# Main_board_V6_0.net
KiCad netlist of a schematic drawn in EAGLE
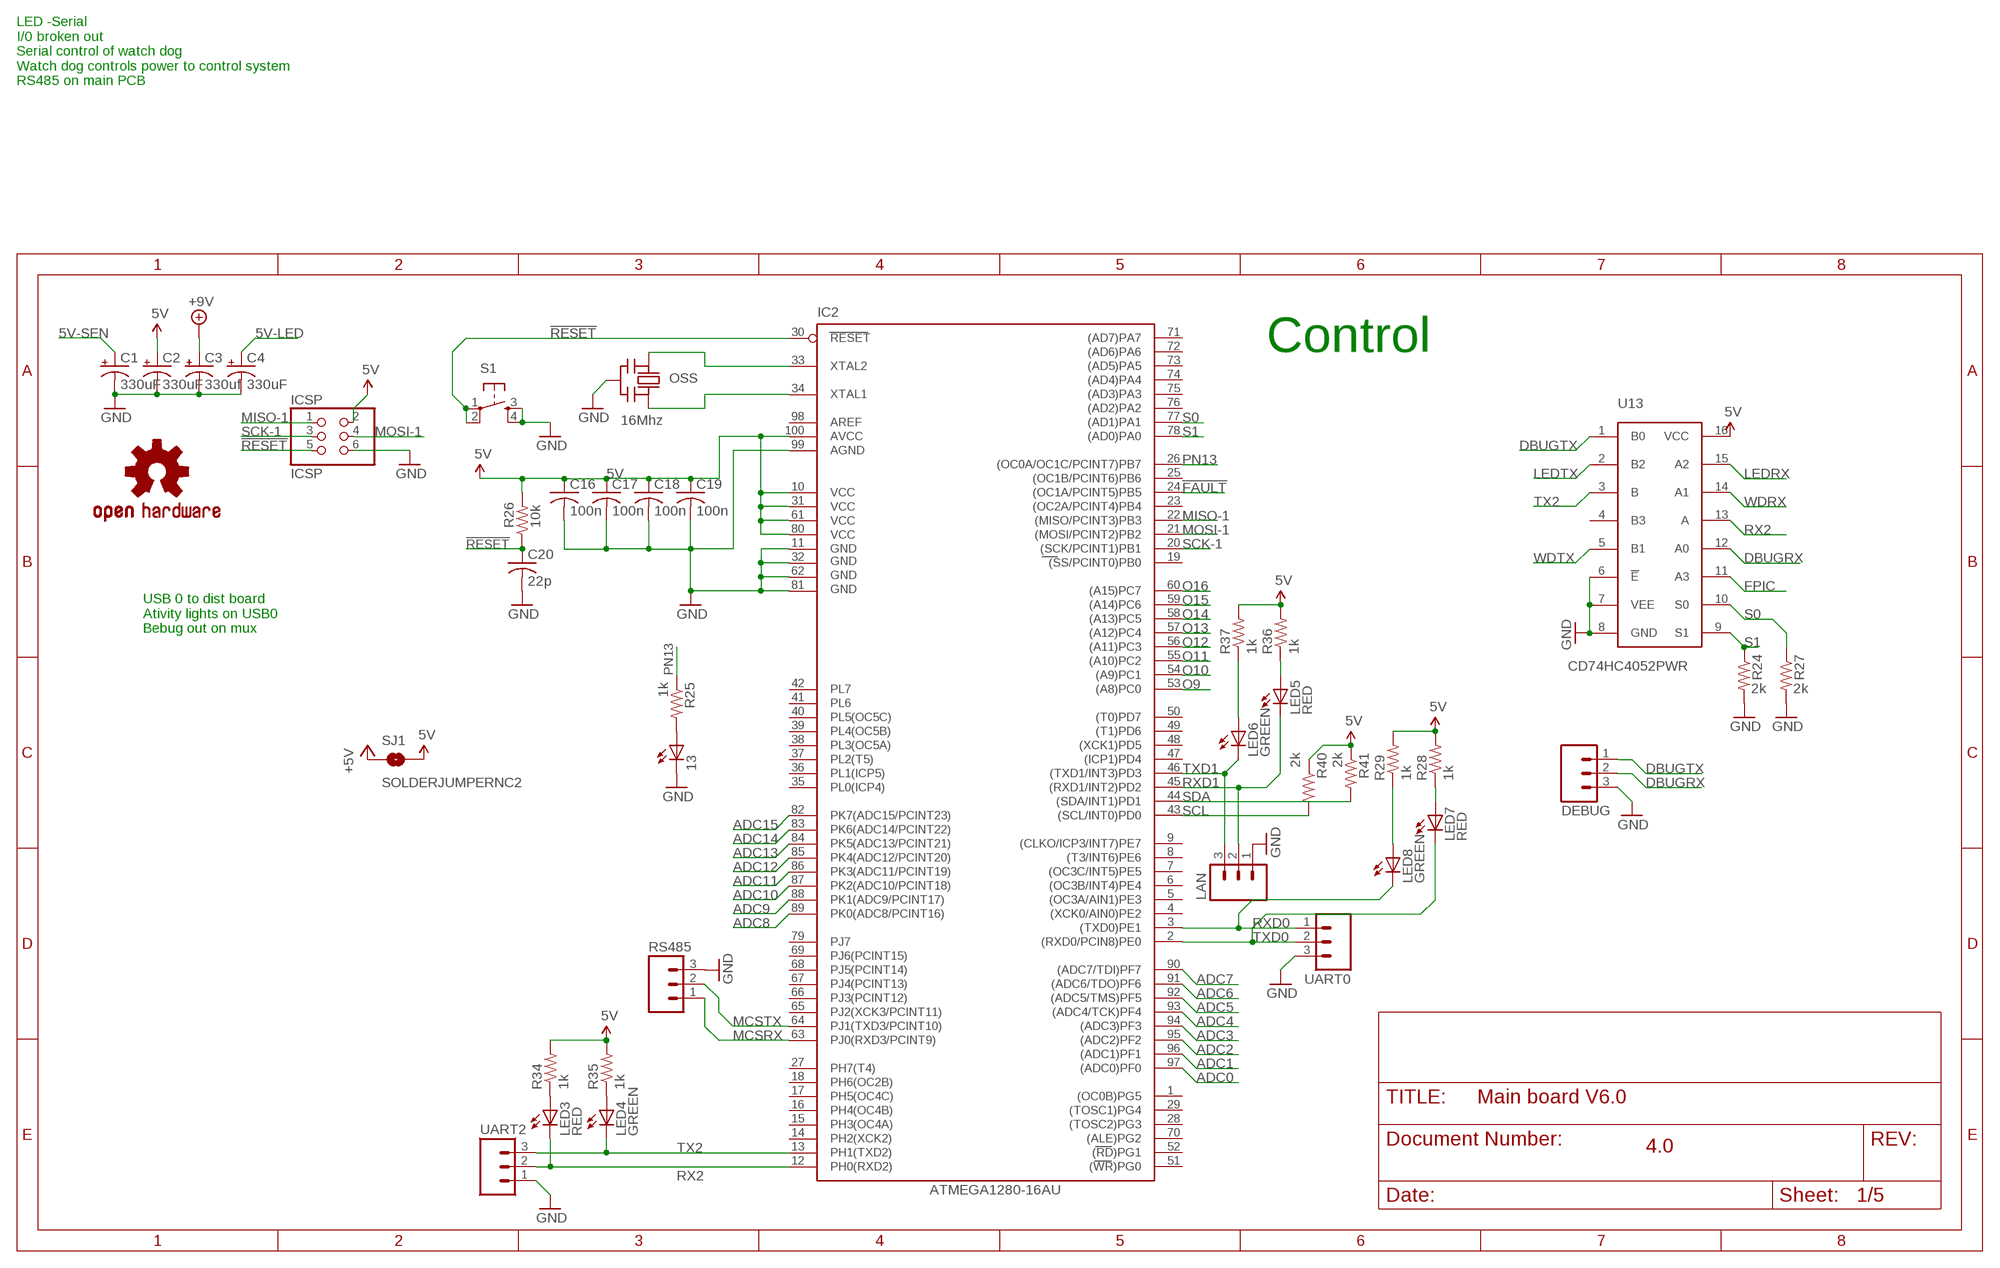
[diagram p0: schematic, sheet 1]
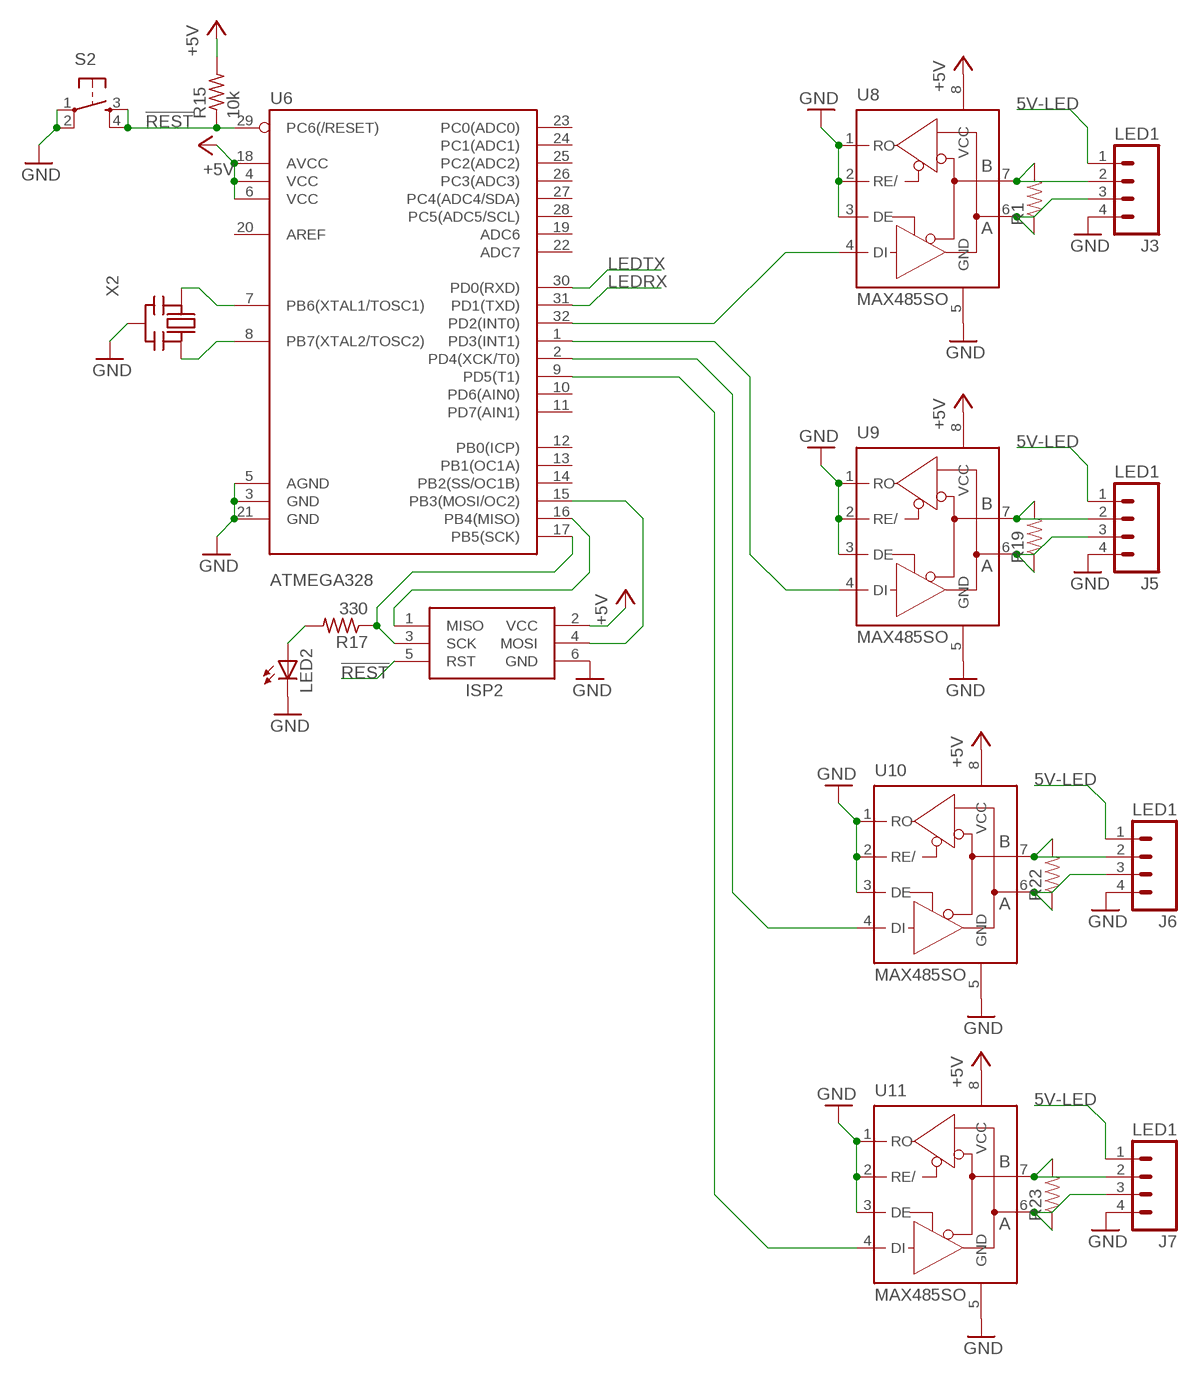
[diagram p1: schematic, sheet 2]
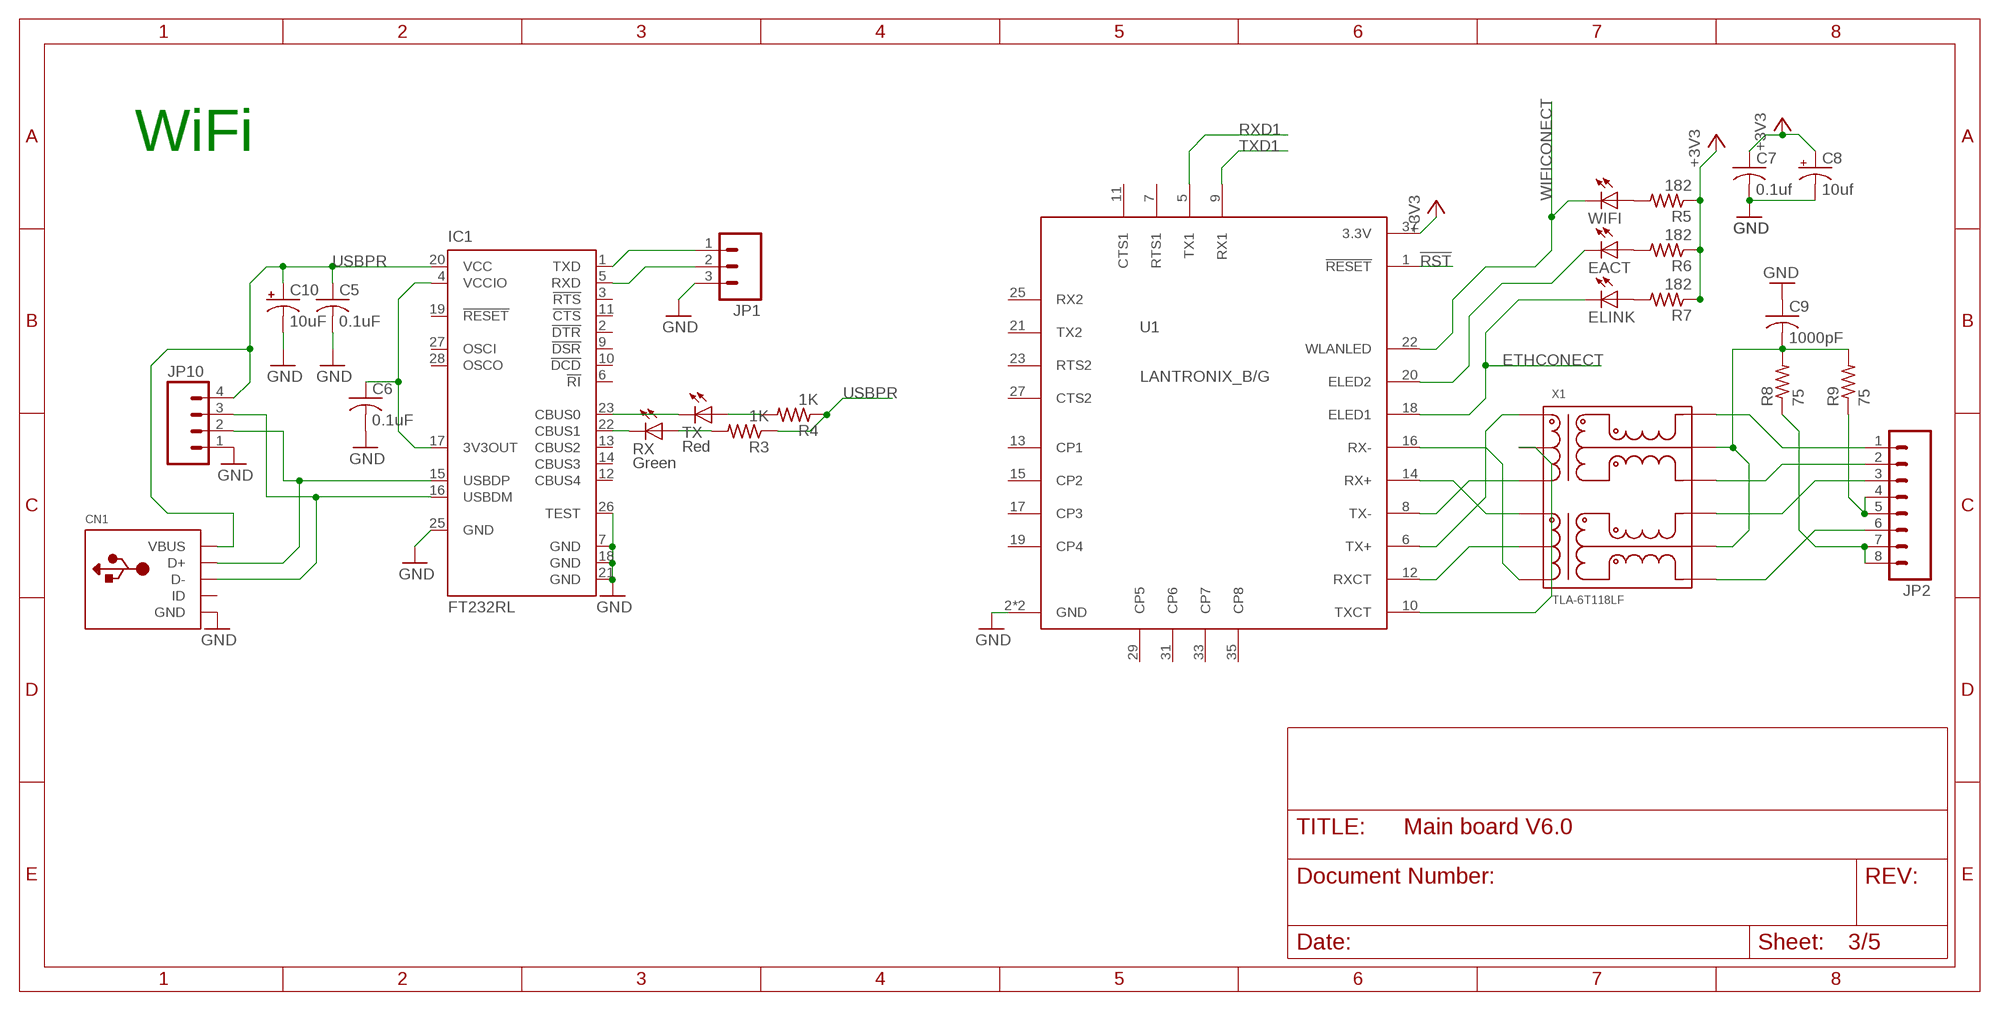
[diagram p2: schematic, sheet 3]
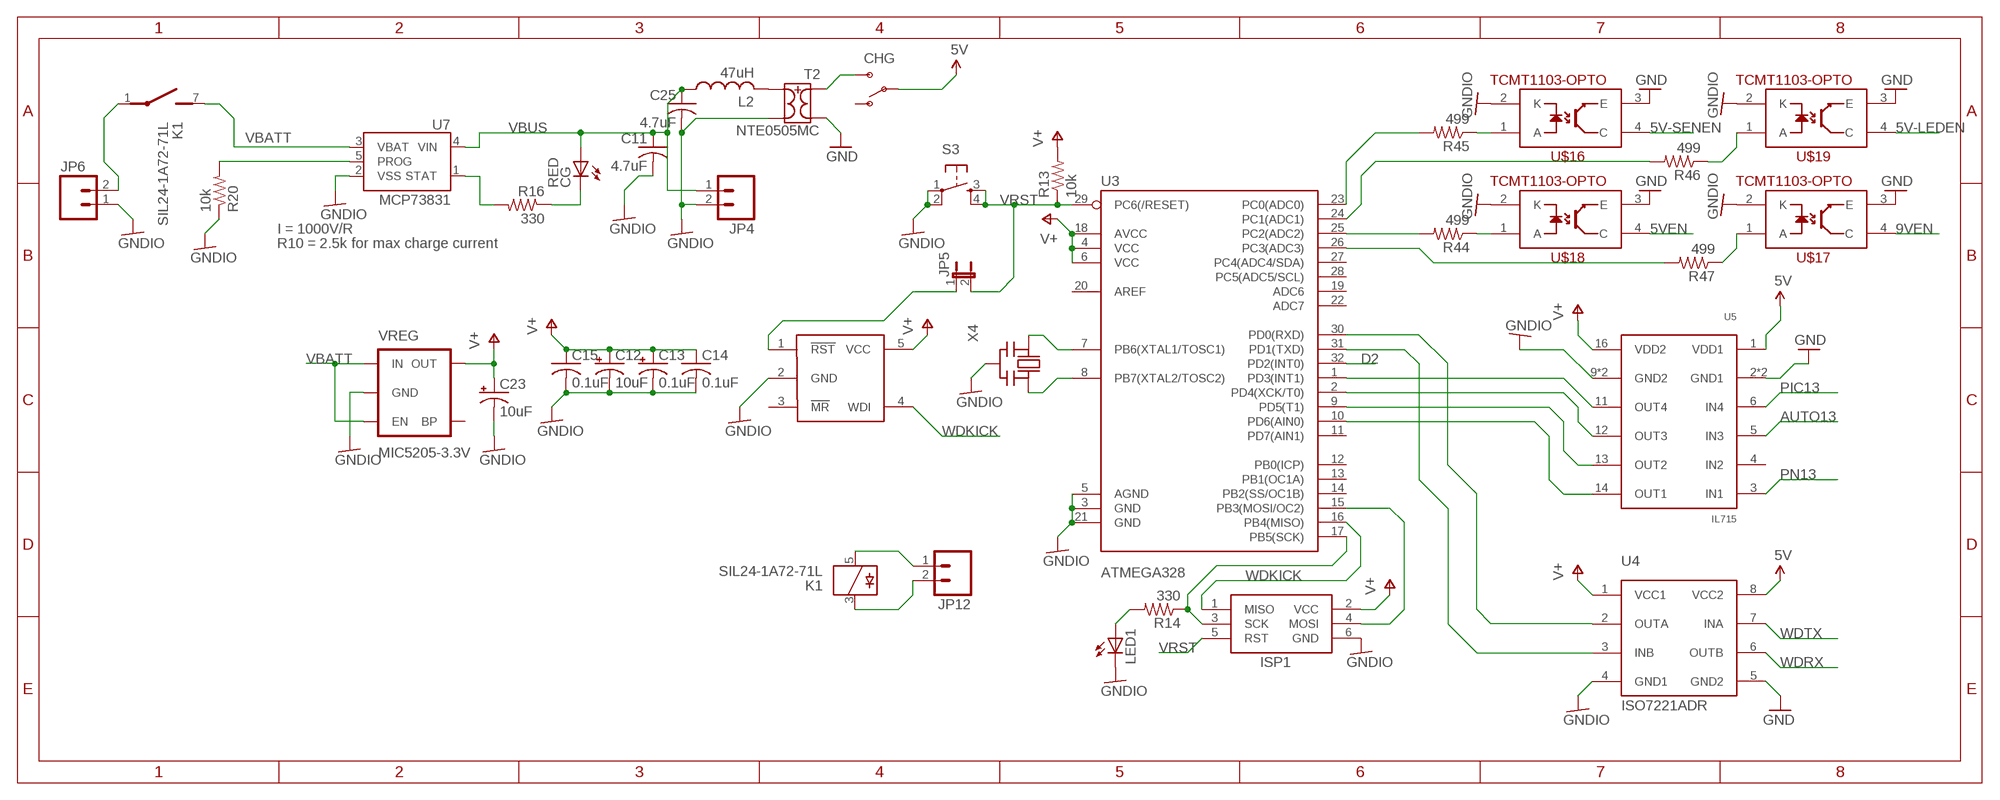
[diagram p3: schematic, sheet 4]
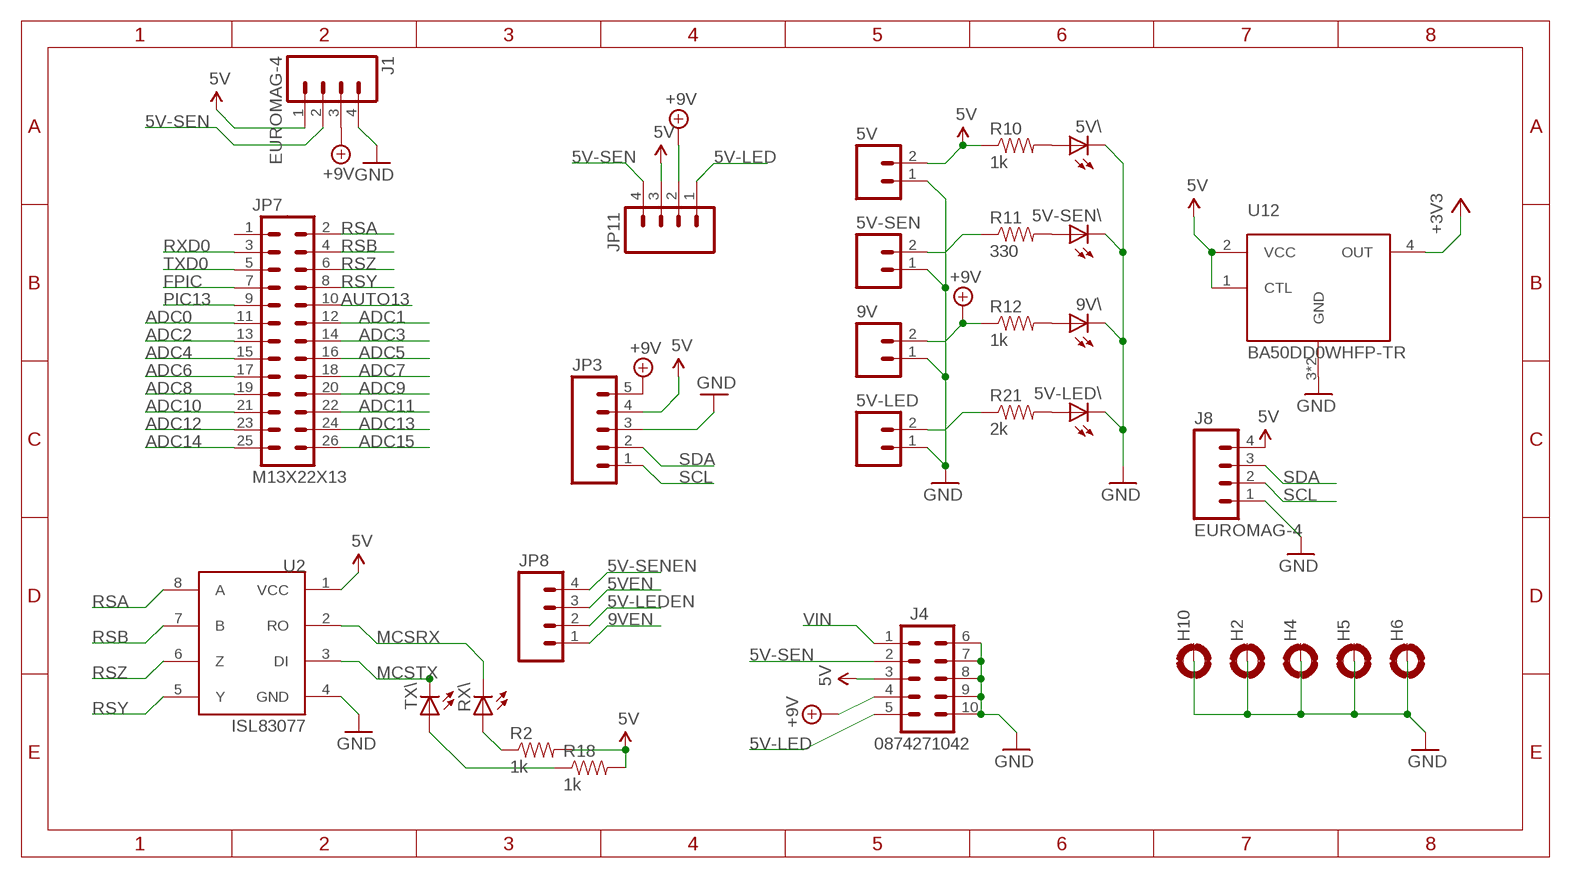
[diagram p4: schematic, sheet 5]

(export (version "E")
  (design (tool "Eeschema 10.0.6"))
  (components
    (comp (ref "5V")
      (value "EUROMAG-290DEG")
      (footprint "eagle-import:M2")
      (libsource (lib "eagle-import") (part "EUROMAG-290DEG"))
    )
    (comp (ref "5V-LED")
      (value "EUROMAG-290DEG")
      (footprint "eagle-import:M2")
      (libsource (lib "eagle-import") (part "EUROMAG-290DEG"))
    )
    (comp (ref "5V-LED\\")
      (value "LEDCHIP-LED0805")
      (footprint "eagle-import:CHIP-LED0805")
      (libsource (lib "eagle-import") (part "LEDCHIP-LED0805"))
    )
    (comp (ref "5V-SEN")
      (value "EUROMAG-290DEG")
      (footprint "eagle-import:M2")
      (libsource (lib "eagle-import") (part "EUROMAG-290DEG"))
    )
    (comp (ref "5V-SEN\\")
      (value "LEDCHIP-LED0805")
      (footprint "eagle-import:CHIP-LED0805")
      (libsource (lib "eagle-import") (part "LEDCHIP-LED0805"))
    )
    (comp (ref "5V\\")
      (value "LEDCHIP-LED0805")
      (footprint "eagle-import:CHIP-LED0805")
      (libsource (lib "eagle-import") (part "LEDCHIP-LED0805"))
    )
    (comp (ref "9V")
      (value "EUROMAG-290DEG")
      (footprint "eagle-import:M2")
      (libsource (lib "eagle-import") (part "EUROMAG-290DEG"))
    )
    (comp (ref "9V\\")
      (value "LEDCHIP-LED0805")
      (footprint "eagle-import:CHIP-LED0805")
      (libsource (lib "eagle-import") (part "LEDCHIP-LED0805"))
    )
    (comp (ref "H2")
      (value "MOUNT-PAD-ROUND2.8")
      (footprint "eagle-import:2,8-PAD")
      (libsource (lib "eagle-import") (part "MOUNT-PAD-ROUND2.8"))
    )
    (comp (ref "H4")
      (value "MOUNT-PAD-ROUND2.8")
      (footprint "eagle-import:2,8-PAD")
      (libsource (lib "eagle-import") (part "MOUNT-PAD-ROUND2.8"))
    )
    (comp (ref "H5")
      (value "MOUNT-PAD-ROUND2.8")
      (footprint "eagle-import:2,8-PAD")
      (libsource (lib "eagle-import") (part "MOUNT-PAD-ROUND2.8"))
    )
    (comp (ref "H6")
      (value "MOUNT-PAD-ROUND2.8")
      (footprint "eagle-import:2,8-PAD")
      (libsource (lib "eagle-import") (part "MOUNT-PAD-ROUND2.8"))
    )
    (comp (ref "H10")
      (value "MOUNT-PAD-ROUND2.8")
      (footprint "eagle-import:2,8-PAD")
      (libsource (lib "eagle-import") (part "MOUNT-PAD-ROUND2.8"))
    )
    (comp (ref "J1")
      (value "EUROMAG-4")
      (footprint "eagle-import:M4")
      (libsource (lib "eagle-import") (part "EUROMAG-4"))
    )
    (comp (ref "J4")
      (value "0874271042")
      (footprint "eagle-import:0874271042")
      (libsource (lib "eagle-import") (part "0874271042"))
    )
    (comp (ref "J8")
      (value "EUROMAG-4")
      (footprint "eagle-import:M4")
      (libsource (lib "eagle-import") (part "EUROMAG-4"))
    )
    (comp (ref "JP3")
      (value "M05LOCK_LONGPADS")
      (footprint "eagle-import:1X05_LOCK_LONGPADS")
      (libsource (lib "eagle-import") (part "M05LOCK_LONGPADS"))
    )
    (comp (ref "JP7")
      (value "M13X22X13")
      (footprint "eagle-import:2X13")
      (libsource (lib "eagle-import") (part "M13X22X13"))
    )
    (comp (ref "JP8")
      (value "M04LOCK")
      (footprint "eagle-import:1X04_LOCK")
      (libsource (lib "eagle-import") (part "SparkFun-Connectors_M04LOCK"))
    )
    (comp (ref "JP11")
      (value "M04POLAR")
      (footprint "eagle-import:MOLEX-1X4")
      (libsource (lib "eagle-import") (part "M04POLAR"))
    )
    (comp (ref "R2")
      (value "1k")
      (footprint "eagle-import:0805")
      (libsource (lib "eagle-import") (part "SparkFun-Passives_RESISTOR0805-RES"))
    )
    (comp (ref "R10")
      (value "1k")
      (footprint "eagle-import:0805")
      (libsource (lib "eagle-import") (part "RESISTOR0805-RES"))
    )
    (comp (ref "R11")
      (value "330")
      (footprint "eagle-import:0805")
      (libsource (lib "eagle-import") (part "RESISTOR0805-RES"))
    )
    (comp (ref "R12")
      (value "1k")
      (footprint "eagle-import:0805")
      (libsource (lib "eagle-import") (part "RESISTOR0805-RES"))
    )
    (comp (ref "R18")
      (value "1k")
      (footprint "eagle-import:0805")
      (libsource (lib "eagle-import") (part "SparkFun-Passives_RESISTOR0805-RES"))
    )
    (comp (ref "R21")
      (value "2k")
      (footprint "eagle-import:0805")
      (libsource (lib "eagle-import") (part "RESISTOR0805-RES"))
    )
    (comp (ref "RX\\")
      (value "LEDCHIP-LED0805")
      (footprint "eagle-import:CHIP-LED0805")
      (libsource (lib "eagle-import") (part "LEDCHIP-LED0805"))
    )
    (comp (ref "TX\\")
      (value "LEDCHIP-LED0805")
      (footprint "eagle-import:CHIP-LED0805")
      (libsource (lib "eagle-import") (part "LEDCHIP-LED0805"))
    )
    (comp (ref "U2")
      (value "ISL83077")
      (footprint "eagle-import:SO08")
      (libsource (lib "eagle-import") (part "ISL83077"))
    )
    (comp (ref "U12")
      (value "BA50DD0WHFP-TR")
      (footprint "eagle-import:HRP5")
      (libsource (lib "eagle-import") (part "BA50DD0WHFP-TR"))
    )
    (comp (ref "ISP2")
      (value "AVRISP-6")
      (footprint "eagle-import:AVRISP")
      (libsource (lib "eagle-import") (part "AVRISP-6"))
    )
    (comp (ref "J3")
      (value "LED1")
      (footprint "eagle-import:M4")
      (libsource (lib "eagle-import") (part "EUROMAG-4"))
    )
    (comp (ref "J5")
      (value "LED1")
      (footprint "eagle-import:M4")
      (libsource (lib "eagle-import") (part "EUROMAG-4"))
    )
    (comp (ref "J6")
      (value "LED1")
      (footprint "eagle-import:M4")
      (libsource (lib "eagle-import") (part "EUROMAG-4"))
    )
    (comp (ref "J7")
      (value "LED1")
      (footprint "eagle-import:M4")
      (libsource (lib "eagle-import") (part "EUROMAG-4"))
    )
    (comp (ref "LED2")
      (value "LEDCHIPLED_0805")
      (footprint "eagle-import:CHIPLED_0805")
      (libsource (lib "eagle-import") (part "LEDCHIPLED_0805"))
    )
    (comp (ref "R1")
      (value "RESISTOR0805-RES")
      (footprint "eagle-import:0805")
      (libsource (lib "eagle-import") (part "SparkFun-Passives_RESISTOR0805-RES"))
    )
    (comp (ref "R15")
      (value "10k")
      (footprint "eagle-import:R0805")
      (libsource (lib "eagle-import") (part "resistor_R-US_R0805"))
    )
    (comp (ref "R17")
      (value "330")
      (footprint "eagle-import:R0805")
      (libsource (lib "eagle-import") (part "resistor_R-US_R0805"))
    )
    (comp (ref "R19")
      (value "RESISTOR0805-RES")
      (footprint "eagle-import:0805")
      (libsource (lib "eagle-import") (part "SparkFun-Passives_RESISTOR0805-RES"))
    )
    (comp (ref "R22")
      (value "RESISTOR0805-RES")
      (footprint "eagle-import:0805")
      (libsource (lib "eagle-import") (part "SparkFun-Passives_RESISTOR0805-RES"))
    )
    (comp (ref "R23")
      (value "RESISTOR0805-RES")
      (footprint "eagle-import:0805")
      (libsource (lib "eagle-import") (part "SparkFun-Passives_RESISTOR0805-RES"))
    )
    (comp (ref "S2")
      (value "TAC_SWITCHPTH")
      (footprint "eagle-import:TACTILE-PTH")
      (libsource (lib "eagle-import") (part "TAC_SWITCHPTH"))
    )
    (comp (ref "U6")
      (value "ATMEGA328")
      (footprint "eagle-import:TQFP32-08")
      (libsource (lib "eagle-import") (part "ATMEGA168"))
    )
    (comp (ref "U8")
      (value "MAX485SO")
      (footprint "eagle-import:SO08")
      (libsource (lib "eagle-import") (part "MAX485SO"))
    )
    (comp (ref "U9")
      (value "MAX485SO")
      (footprint "eagle-import:SO08")
      (libsource (lib "eagle-import") (part "MAX485SO"))
    )
    (comp (ref "U10")
      (value "MAX485SO")
      (footprint "eagle-import:SO08")
      (libsource (lib "eagle-import") (part "MAX485SO"))
    )
    (comp (ref "U11")
      (value "MAX485SO")
      (footprint "eagle-import:SO08")
      (libsource (lib "eagle-import") (part "MAX485SO"))
    )
    (comp (ref "X2")
      (value "CERMOSCILL-AWCSR")
      (footprint "eagle-import:AWCSR")
      (libsource (lib "eagle-import") (part "CERMOSCILL-AWCSR"))
    )
    (comp (ref "C5")
      (value "0.1uF")
      (footprint "eagle-import:C0805K")
      (libsource (lib "eagle-import") (part "C-USC0805K"))
    )
    (comp (ref "C6")
      (value "0.1uF")
      (footprint "eagle-import:C0805K")
      (libsource (lib "eagle-import") (part "C-USC0805K"))
    )
    (comp (ref "C7")
      (value "0.1uf")
      (footprint "eagle-import:C0805K")
      (libsource (lib "eagle-import") (part "C-USC0805K"))
    )
    (comp (ref "C8")
      (value "10uf")
      (footprint "eagle-import:EIA3528")
      (libsource (lib "eagle-import") (part "CAP_POL3528"))
    )
    (comp (ref "C9")
      (value "1000pF")
      (footprint "eagle-import:C1812")
      (libsource (lib "eagle-import") (part "C-USC1812"))
    )
    (comp (ref "C10")
      (value "10uF")
      (footprint "eagle-import:EIA3528-KIT")
      (libsource (lib "eagle-import") (part "CAP_POL3528-KIT"))
    )
    (comp (ref "CN1")
      (value "USBMINIB")
      (footprint "eagle-import:USB-MINIB")
      (libsource (lib "eagle-import") (part "USBMINIB"))
    )
    (comp (ref "EACT")
      (value "LEDCHIP-LED0805")
      (footprint "eagle-import:CHIP-LED0805")
      (libsource (lib "eagle-import") (part "LEDCHIP-LED0805"))
    )
    (comp (ref "ELINK")
      (value "LEDCHIP-LED0805")
      (footprint "eagle-import:CHIP-LED0805")
      (libsource (lib "eagle-import") (part "LEDCHIP-LED0805"))
    )
    (comp (ref "IC1")
      (value "FT232RL")
      (footprint "eagle-import:SSOP28")
      (libsource (lib "eagle-import") (part "FT232RL"))
    )
    (comp (ref "JP1")
      (value "M03POLAR")
      (footprint "eagle-import:MOLEX-1X3")
      (libsource (lib "eagle-import") (part "M03POLAR"))
    )
    (comp (ref "JP2")
      (value "M08LOCK")
      (footprint "eagle-import:1X08_LOCK")
      (libsource (lib "eagle-import") (part "M08LOCK"))
    )
    (comp (ref "JP10")
      (value "M04POLAR")
      (footprint "eagle-import:MOLEX-1X4")
      (libsource (lib "eagle-import") (part "M04POLAR"))
    )
    (comp (ref "R3")
      (value "1K")
      (footprint "eagle-import:R0805")
      (libsource (lib "eagle-import") (part "R-US_R0805"))
    )
    (comp (ref "R4")
      (value "1K")
      (footprint "eagle-import:R0805")
      (libsource (lib "eagle-import") (part "R-US_R0805"))
    )
    (comp (ref "R5")
      (value "182")
      (footprint "eagle-import:R0805")
      (libsource (lib "eagle-import") (part "R-US_R0805"))
    )
    (comp (ref "R6")
      (value "182")
      (footprint "eagle-import:R0805")
      (libsource (lib "eagle-import") (part "R-US_R0805"))
    )
    (comp (ref "R7")
      (value "182")
      (footprint "eagle-import:R0805")
      (libsource (lib "eagle-import") (part "R-US_R0805"))
    )
    (comp (ref "R8")
      (value "75")
      (footprint "eagle-import:R0805")
      (libsource (lib "eagle-import") (part "R-US_R0805"))
    )
    (comp (ref "R9")
      (value "75")
      (footprint "eagle-import:R0805")
      (libsource (lib "eagle-import") (part "R-US_R0805"))
    )
    (comp (ref "RX")
      (value "Green")
      (footprint "eagle-import:CHIP-LED0805")
      (libsource (lib "eagle-import") (part "LEDCHIP-LED0805"))
    )
    (comp (ref "TX")
      (value "Red")
      (footprint "eagle-import:CHIP-LED0805")
      (libsource (lib "eagle-import") (part "LEDCHIP-LED0805"))
    )
    (comp (ref "U1")
      (value "LANTRONIX_B/G")
      (footprint "eagle-import:LANA_BTH")
      (libsource (lib "eagle-import") (part "LANTRONIX_A/B"))
    )
    (comp (ref "WIFI")
      (value "LEDCHIP-LED0805")
      (footprint "eagle-import:CHIP-LED0805")
      (libsource (lib "eagle-import") (part "LEDCHIP-LED0805"))
    )
    (comp (ref "X1")
      (value "TLA-6T118LF")
      (footprint "eagle-import:SO-16MOD")
      (libsource (lib "eagle-import") (part "TLA-6T118LF"))
    )
    (comp (ref "13")
      (value "LEDCHIP-LED0805")
      (footprint "eagle-import:CHIP-LED0805")
      (libsource (lib "eagle-import") (part "LEDCHIP-LED0805"))
    )
    (comp (ref "C1")
      (value "330uF")
      (footprint "eagle-import:140CLH-0810")
      (libsource (lib "eagle-import") (part "CPOL-US140CLH-0810"))
    )
    (comp (ref "C2")
      (value "330uF")
      (footprint "eagle-import:140CLH-0810")
      (libsource (lib "eagle-import") (part "CPOL-US140CLH-0810"))
    )
    (comp (ref "C3")
      (value "330uf")
      (footprint "eagle-import:140CLH-0810")
      (libsource (lib "eagle-import") (part "CPOL-US140CLH-0810"))
    )
    (comp (ref "C4")
      (value "330uF")
      (footprint "eagle-import:140CLH-0810")
      (libsource (lib "eagle-import") (part "CPOL-US140CLH-0810"))
    )
    (comp (ref "C16")
      (value "100n")
      (footprint "eagle-import:C0805")
      (libsource (lib "eagle-import") (part "C-USC0805"))
    )
    (comp (ref "C17")
      (value "100n")
      (footprint "eagle-import:C0805")
      (libsource (lib "eagle-import") (part "C-USC0805"))
    )
    (comp (ref "C18")
      (value "100n")
      (footprint "eagle-import:C0805")
      (libsource (lib "eagle-import") (part "C-USC0805"))
    )
    (comp (ref "C19")
      (value "100n")
      (footprint "eagle-import:C0805")
      (libsource (lib "eagle-import") (part "C-USC0805"))
    )
    (comp (ref "C20")
      (value "22p")
      (footprint "eagle-import:C0805")
      (libsource (lib "eagle-import") (part "C-USC0805"))
    )
    (comp (ref "DEBUG")
      (value "M03LOCK")
      (footprint "eagle-import:1X03_LOCK")
      (libsource (lib "eagle-import") (part "M03LOCK"))
    )
    (comp (ref "IC2")
      (value "ATMEGA1280-16AU")
      (footprint "eagle-import:TQFP100")
      (libsource (lib "eagle-import") (part "ATMEGAAU1280-16"))
    )
    (comp (ref "ICSP")
      (value "ICSP")
      (footprint "eagle-import:2X03")
      (libsource (lib "eagle-import") (part "PINHD-2X3"))
    )
    (comp (ref "LAN")
      (value "M03LOCK")
      (footprint "eagle-import:1X03_LOCK")
      (libsource (lib "eagle-import") (part "M03LOCK"))
    )
    (comp (ref "LED3")
      (value "RED")
      (footprint "eagle-import:CHIP-LED0805")
      (libsource (lib "eagle-import") (part "LEDCHIP-LED0805"))
    )
    (comp (ref "LED4")
      (value "GREEN")
      (footprint "eagle-import:CHIP-LED0805")
      (libsource (lib "eagle-import") (part "LEDCHIP-LED0805"))
    )
    (comp (ref "LED5")
      (value "RED")
      (footprint "eagle-import:CHIP-LED0805")
      (libsource (lib "eagle-import") (part "LEDCHIP-LED0805"))
    )
    (comp (ref "LED6")
      (value "GREEN")
      (footprint "eagle-import:CHIP-LED0805")
      (libsource (lib "eagle-import") (part "LEDCHIP-LED0805"))
    )
    (comp (ref "LED7")
      (value "RED")
      (footprint "eagle-import:CHIP-LED0805")
      (libsource (lib "eagle-import") (part "LEDCHIP-LED0805"))
    )
    (comp (ref "LED8")
      (value "GREEN")
      (footprint "eagle-import:CHIP-LED0805")
      (libsource (lib "eagle-import") (part "LEDCHIP-LED0805"))
    )
    (comp (ref "OSS")
      (value "16Mhz")
      (footprint "eagle-import:AWCSR")
      (libsource (lib "eagle-import") (part "CERMOSCILL-AWCSR"))
    )
    (comp (ref "R24")
      (value "2k")
      (footprint "eagle-import:R0805")
      (libsource (lib "eagle-import") (part "R-US_R0805"))
    )
    (comp (ref "R25")
      (value "1k")
      (footprint "eagle-import:R0805")
      (libsource (lib "eagle-import") (part "R-US_R0805"))
    )
    (comp (ref "R26")
      (value "10k")
      (footprint "eagle-import:R0805")
      (libsource (lib "eagle-import") (part "R-US_R0805"))
    )
    (comp (ref "R27")
      (value "2k")
      (footprint "eagle-import:R0805")
      (libsource (lib "eagle-import") (part "R-US_R0805"))
    )
    (comp (ref "R28")
      (value "1k")
      (footprint "eagle-import:R0805")
      (libsource (lib "eagle-import") (part "R-US_R0805"))
    )
    (comp (ref "R29")
      (value "1k")
      (footprint "eagle-import:R0805")
      (libsource (lib "eagle-import") (part "R-US_R0805"))
    )
    (comp (ref "R34")
      (value "1k")
      (footprint "eagle-import:R0805")
      (libsource (lib "eagle-import") (part "R-US_R0805"))
    )
    (comp (ref "R35")
      (value "1k")
      (footprint "eagle-import:R0805")
      (libsource (lib "eagle-import") (part "R-US_R0805"))
    )
    (comp (ref "R36")
      (value "1k")
      (footprint "eagle-import:R0805")
      (libsource (lib "eagle-import") (part "R-US_R0805"))
    )
    (comp (ref "R37")
      (value "1k")
      (footprint "eagle-import:R0805")
      (libsource (lib "eagle-import") (part "R-US_R0805"))
    )
    (comp (ref "R40")
      (value "2k")
      (footprint "eagle-import:R0805")
      (libsource (lib "eagle-import") (part "R-US_R0805"))
    )
    (comp (ref "R41")
      (value "2k")
      (footprint "eagle-import:R0805")
      (libsource (lib "eagle-import") (part "R-US_R0805"))
    )
    (comp (ref "RS485")
      (value "M03LOCK")
      (footprint "eagle-import:1X03_LOCK")
      (libsource (lib "eagle-import") (part "M03LOCK"))
    )
    (comp (ref "S1")
      (value "TAC_SWITCHSMD")
      (footprint "eagle-import:TACTILE_SWITCH_SMD")
      (libsource (lib "eagle-import") (part "TAC_SWITCHSMD"))
    )
    (comp (ref "SJ1")
      (value "SOLDERJUMPERNC2")
      (footprint "eagle-import:SJ_2S-NOTRACE")
      (libsource (lib "eagle-import") (part "SOLDERJUMPERNC2"))
    )
    (comp (ref "U$3")
      (value "OSHW-LOGOL")
      (footprint "eagle-import:OSHW-LOGO-L")
      (libsource (lib "eagle-import") (part "OSHW-LOGOL"))
    )
    (comp (ref "U13")
      (value "CD74HC4052PWR")
      (footprint "eagle-import:TSSOP-16")
      (libsource (lib "eagle-import") (part "CD74HC4052PWR"))
    )
    (comp (ref "UART0")
      (value "M03LOCK")
      (footprint "eagle-import:1X03_LOCK")
      (libsource (lib "eagle-import") (part "M03LOCK"))
    )
    (comp (ref "UART2")
      (value "M03POLAR")
      (footprint "eagle-import:MOLEX-1X3")
      (libsource (lib "eagle-import") (part "M03POLAR"))
    )
    (comp (ref "C11")
      (value "4.7uF")
      (footprint "eagle-import:C0603")
      (libsource (lib "eagle-import") (part "resistor_C-USC0603"))
    )
    (comp (ref "C12")
      (value "10uF")
      (footprint "eagle-import:CT3528")
      (libsource (lib "eagle-import") (part "CPOL-USCT3528"))
    )
    (comp (ref "C13")
      (value "0.1uF")
      (footprint "eagle-import:CT3528")
      (libsource (lib "eagle-import") (part "CPOL-USCT3528"))
    )
    (comp (ref "C14")
      (value "0.1uF")
      (footprint "eagle-import:C0805")
      (libsource (lib "eagle-import") (part "C-USC0805"))
    )
    (comp (ref "C15")
      (value "0.1uF")
      (footprint "eagle-import:C0805")
      (libsource (lib "eagle-import") (part "C-USC0805"))
    )
    (comp (ref "C23")
      (value "10uF")
      (footprint "eagle-import:CT3528")
      (libsource (lib "eagle-import") (part "CPOL-USCT3528"))
    )
    (comp (ref "C25")
      (value "4.7uF")
      (footprint "eagle-import:C0603")
      (libsource (lib "eagle-import") (part "resistor_C-USC0603"))
    )
    (comp (ref "CG")
      (value "RED")
      (footprint "eagle-import:SML0805")
      (libsource (lib "eagle-import") (part "LEDSML0805"))
    )
    (comp (ref "CHG")
      (value "SWITCH-SPSTPTH")
      (footprint "eagle-import:SWITCH-SPDT")
      (libsource (lib "eagle-import") (part "SWITCH-SPSTPTH"))
    )
    (comp (ref "ISP1")
      (value "AVRISP-6")
      (footprint "eagle-import:AVRISP")
      (libsource (lib "eagle-import") (part "AVRISP-6"))
    )
    (comp (ref "JP4")
      (value "M021X02_NO_SILK")
      (footprint "eagle-import:1X02_NO_SILK")
      (libsource (lib "eagle-import") (part "M021X02_NO_SILK"))
    )
    (comp (ref "JP5")
      (value "JUMPER-2PTH_LOCK")
      (footprint "eagle-import:1X02_LOCK")
      (libsource (lib "eagle-import") (part "JUMPER-2PTH_LOCK"))
    )
    (comp (ref "JP6")
      (value "M02-JST-2MM-SMT")
      (footprint "eagle-import:JST-2-SMD")
      (libsource (lib "eagle-import") (part "M02-JST-2MM-SMT"))
    )
    (comp (ref "JP12")
      (value "M02POLAR_LOCK")
      (footprint "eagle-import:MOLEX-1X2_LOCK")
      (libsource (lib "eagle-import") (part "M02POLAR_LOCK"))
    )
    (comp (ref "K1")
      (value "SIL24-1A72-71L")
      (footprint "eagle-import:REED")
      (libsource (lib "eagle-import") (part "35701331"))
    )
    (comp (ref "L2")
      (value "47uH")
      (footprint "eagle-import:L2012C")
      (libsource (lib "eagle-import") (part "L-USL2012C"))
    )
    (comp (ref "LED1")
      (value "LEDCHIPLED_0805")
      (footprint "eagle-import:CHIPLED_0805")
      (libsource (lib "eagle-import") (part "LEDCHIPLED_0805"))
    )
    (comp (ref "R13")
      (value "10k")
      (footprint "eagle-import:R0805")
      (libsource (lib "eagle-import") (part "resistor_R-US_R0805"))
    )
    (comp (ref "R14")
      (value "330")
      (footprint "eagle-import:R0805")
      (libsource (lib "eagle-import") (part "resistor_R-US_R0805"))
    )
    (comp (ref "R16")
      (value "330")
      (footprint "eagle-import:R0805")
      (libsource (lib "eagle-import") (part "resistor_R-US_R0805"))
    )
    (comp (ref "R20")
      (value "10k")
      (footprint "eagle-import:R0805")
      (libsource (lib "eagle-import") (part "resistor_R-US_R0805"))
    )
    (comp (ref "R44")
      (value "499")
      (footprint "eagle-import:R0805")
      (libsource (lib "eagle-import") (part "resistor_R-US_R0805"))
    )
    (comp (ref "R45")
      (value "499")
      (footprint "eagle-import:R0805")
      (libsource (lib "eagle-import") (part "resistor_R-US_R0805"))
    )
    (comp (ref "R46")
      (value "499")
      (footprint "eagle-import:R0805")
      (libsource (lib "eagle-import") (part "resistor_R-US_R0805"))
    )
    (comp (ref "R47")
      (value "499")
      (footprint "eagle-import:R0805")
      (libsource (lib "eagle-import") (part "resistor_R-US_R0805"))
    )
    (comp (ref "S3")
      (value "TAC_SWITCHPTH")
      (footprint "eagle-import:TACTILE-PTH")
      (libsource (lib "eagle-import") (part "TAC_SWITCHPTH"))
    )
    (comp (ref "T2")
      (value "NTE0505MC")
      (footprint "eagle-import:SO-8FT")
      (libsource (lib "eagle-import") (part "NTE0505MC"))
    )
    (comp (ref "U$16")
      (value "TCMT1103-OPTO")
      (footprint "eagle-import:SSOP-4")
      (libsource (lib "eagle-import") (part "TCMT1103-OPTO"))
    )
    (comp (ref "U$17")
      (value "TCMT1103-OPTO")
      (footprint "eagle-import:SSOP-4")
      (libsource (lib "eagle-import") (part "TCMT1103-OPTO"))
    )
    (comp (ref "U$18")
      (value "TCMT1103-OPTO")
      (footprint "eagle-import:SSOP-4")
      (libsource (lib "eagle-import") (part "TCMT1103-OPTO"))
    )
    (comp (ref "U$19")
      (value "TCMT1103-OPTO")
      (footprint "eagle-import:SSOP-4")
      (libsource (lib "eagle-import") (part "TCMT1103-OPTO"))
    )
    (comp (ref "U3")
      (value "ATMEGA328")
      (footprint "eagle-import:TQFP32-08")
      (libsource (lib "eagle-import") (part "ATMEGA168"))
    )
    (comp (ref "U4")
      (value "ISO7221ADR")
      (footprint "eagle-import:SOIC-8")
      (libsource (lib "eagle-import") (part "ISO7221ADR"))
    )
    (comp (ref "U5")
      (value "IL715")
      (footprint "eagle-import:S016")
      (libsource (lib "eagle-import") (part "IL715"))
    )
    (comp (ref "U7")
      (value "MCP73831")
      (footprint "eagle-import:SOT23-5")
      (libsource (lib "eagle-import") (part "MCP73831"))
    )
    (comp (ref "U20")
      (value "MAX823")
      (footprint "eagle-import:SOT23-5L")
      (libsource (lib "eagle-import") (part "MAX823"))
    )
    (comp (ref "VREG")
      (value "MIC5205-3.3V")
      (footprint "eagle-import:SOT23-5")
      (libsource (lib "eagle-import") (part "V_REG_LDOSMD"))
    )
    (comp (ref "X4")
      (value "CERMOSCILL-CSTCRG")
      (footprint "eagle-import:CSTCR-G")
      (libsource (lib "eagle-import") (part "CERMOSCILL-CSTCRG"))
    )
  )
  (nets
    (net (code "1") (name "+3V3") (class "Default")
      (node (ref "C7") (pin "1") (pinfunction "1_1") (pintype "passive"))
      (node (ref "C8") (pin "A") (pinfunction "+_A") (pintype "passive"))
      (node (ref "R5") (pin "1") (pinfunction "1_1") (pintype "passive"))
      (node (ref "R6") (pin "1") (pinfunction "1_1") (pintype "passive"))
      (node (ref "R7") (pin "1") (pinfunction "1_1") (pintype "passive"))
      (node (ref "U1") (pin "37") (pinfunction "3.3V_37") (pintype "bidirectional"))
      (node (ref "U12") (pin "4") (pinfunction "OUT_4") (pintype "bidirectional"))
    )
    (net (code "2") (name "+5V") (class "Default")
      (node (ref "ISP2") (pin "2") (pinfunction "VCC_2") (pintype "power_in"))
      (node (ref "R15") (pin "2") (pinfunction "2_2") (pintype "passive"))
      (node (ref "SJ1") (pin "1") (pinfunction "1_1") (pintype "passive"))
      (node (ref "U10") (pin "8") (pinfunction "VCC_8") (pintype "bidirectional"))
      (node (ref "U11") (pin "8") (pinfunction "VCC_8") (pintype "bidirectional"))
      (node (ref "U6") (pin "18") (pinfunction "AVCC_18") (pintype "bidirectional"))
      (node (ref "U6") (pin "4") (pinfunction "VCC_4") (pintype "bidirectional"))
      (node (ref "U6") (pin "6") (pinfunction "VCC_6") (pintype "bidirectional"))
      (node (ref "U8") (pin "8") (pinfunction "VCC_8") (pintype "bidirectional"))
      (node (ref "U9") (pin "8") (pinfunction "VCC_8") (pintype "bidirectional"))
    )
    (net (code "3") (name "+9V") (class "Default")
      (node (ref "9V") (pin "2") (pinfunction "2_2") (pintype "passive"))
      (node (ref "C3") (pin "+") (pinfunction "+_+") (pintype "passive"))
      (node (ref "J1") (pin "3") (pinfunction "3_3") (pintype "passive"))
      (node (ref "J4") (pin "4") (pinfunction "4_4") (pintype "passive"))
      (node (ref "JP11") (pin "2") (pinfunction "2_2") (pintype "passive"))
      (node (ref "JP3") (pin "5") (pinfunction "5_5") (pintype "passive"))
      (node (ref "R12") (pin "1") (pinfunction "1_1") (pintype "passive"))
    )
    (net (code "4") (name "5V") (class "Default")
      (node (ref "5V") (pin "2") (pinfunction "2_2") (pintype "passive"))
      (node (ref "C16") (pin "1") (pinfunction "1_1") (pintype "passive"))
      (node (ref "C17") (pin "1") (pinfunction "1_1") (pintype "passive"))
      (node (ref "C18") (pin "1") (pinfunction "1_1") (pintype "passive"))
      (node (ref "C19") (pin "1") (pinfunction "1_1") (pintype "passive"))
      (node (ref "C2") (pin "+") (pinfunction "+_+") (pintype "passive"))
      (node (ref "CHG") (pin "2") (pinfunction "P_2") (pintype "passive"))
      (node (ref "IC2") (pin "10") (pinfunction "VCC_10") (pintype "power_in"))
      (node (ref "IC2") (pin "100") (pinfunction "AVCC_100") (pintype "power_in"))
      (node (ref "IC2") (pin "31") (pinfunction "VCC1_31") (pintype "power_in"))
      (node (ref "IC2") (pin "61") (pinfunction "VCC2_61") (pintype "power_in"))
      (node (ref "IC2") (pin "80") (pinfunction "VCC3_80") (pintype "power_in"))
      (node (ref "ICSP") (pin "2") (pinfunction "2_2") (pintype "passive"))
      (node (ref "J1") (pin "1") (pinfunction "1_1") (pintype "passive"))
      (node (ref "J4") (pin "3") (pinfunction "3_3") (pintype "passive"))
      (node (ref "J8") (pin "4") (pinfunction "4_4") (pintype "passive"))
      (node (ref "JP11") (pin "3") (pinfunction "3_3") (pintype "passive"))
      (node (ref "JP3") (pin "4") (pinfunction "4_4") (pintype "passive"))
      (node (ref "R10") (pin "1") (pinfunction "1_1") (pintype "passive"))
      (node (ref "R18") (pin "2") (pinfunction "2_2") (pintype "passive"))
      (node (ref "R2") (pin "2") (pinfunction "2_2") (pintype "passive"))
      (node (ref "R26") (pin "2") (pinfunction "2_2") (pintype "passive"))
      (node (ref "R28") (pin "2") (pinfunction "2_2") (pintype "passive"))
      (node (ref "R29") (pin "2") (pinfunction "2_2") (pintype "passive"))
      (node (ref "R34") (pin "2") (pinfunction "2_2") (pintype "passive"))
      (node (ref "R35") (pin "2") (pinfunction "2_2") (pintype "passive"))
      (node (ref "R36") (pin "2") (pinfunction "2_2") (pintype "passive"))
      (node (ref "R37") (pin "2") (pinfunction "2_2") (pintype "passive"))
      (node (ref "R40") (pin "1") (pinfunction "1_1") (pintype "passive"))
      (node (ref "R41") (pin "1") (pinfunction "1_1") (pintype "passive"))
      (node (ref "SJ1") (pin "2") (pinfunction "2_2") (pintype "passive"))
      (node (ref "U12") (pin "1") (pinfunction "CTL_1") (pintype "bidirectional"))
      (node (ref "U12") (pin "2") (pinfunction "VCC_2") (pintype "bidirectional"))
      (node (ref "U13") (pin "16") (pinfunction "VCC_16") (pintype "bidirectional"))
      (node (ref "U2") (pin "1") (pinfunction "VCC_1") (pintype "bidirectional"))
      (node (ref "U4") (pin "8") (pinfunction "VCC2_8") (pintype "bidirectional"))
      (node (ref "U5") (pin "1") (pinfunction "VDD1_1") (pintype "bidirectional"))
    )
    (net (code "5") (name "5V-LED") (class "Default")
      (node (ref "5V-LED") (pin "2") (pinfunction "2_2") (pintype "passive"))
      (node (ref "C4") (pin "+") (pinfunction "+_+") (pintype "passive"))
      (node (ref "J3") (pin "1") (pinfunction "1_1") (pintype "passive"))
      (node (ref "J4") (pin "5") (pinfunction "5_5") (pintype "passive"))
      (node (ref "J5") (pin "1") (pinfunction "1_1") (pintype "passive"))
      (node (ref "J6") (pin "1") (pinfunction "1_1") (pintype "passive"))
      (node (ref "J7") (pin "1") (pinfunction "1_1") (pintype "passive"))
      (node (ref "JP11") (pin "1") (pinfunction "1_1") (pintype "passive"))
      (node (ref "R21") (pin "1") (pinfunction "1_1") (pintype "passive"))
    )
    (net (code "6") (name "5V-LEDEN") (class "Default")
      (node (ref "JP8") (pin "2") (pinfunction "2_2") (pintype "passive"))
      (node (ref "U$19") (pin "4") (pinfunction "C_4") (pintype "bidirectional"))
    )
    (net (code "7") (name "5V-SEN") (class "Default")
      (node (ref "5V-SEN") (pin "2") (pinfunction "2_2") (pintype "passive"))
      (node (ref "C1") (pin "+") (pinfunction "+_+") (pintype "passive"))
      (node (ref "J1") (pin "2") (pinfunction "2_2") (pintype "passive"))
      (node (ref "J4") (pin "2") (pinfunction "2_2") (pintype "passive"))
      (node (ref "JP11") (pin "4") (pinfunction "4_4") (pintype "passive"))
      (node (ref "R11") (pin "1") (pinfunction "1_1") (pintype "passive"))
    )
    (net (code "8") (name "5V-SENEN") (class "Default")
      (node (ref "JP8") (pin "4") (pinfunction "4_4") (pintype "passive"))
      (node (ref "U$16") (pin "4") (pinfunction "C_4") (pintype "bidirectional"))
    )
    (net (code "9") (name "5VEN") (class "Default")
      (node (ref "JP8") (pin "3") (pinfunction "3_3") (pintype "passive"))
      (node (ref "U$18") (pin "4") (pinfunction "C_4") (pintype "bidirectional"))
    )
    (net (code "10") (name "9VEN") (class "Default")
      (node (ref "JP8") (pin "1") (pinfunction "1_1") (pintype "passive"))
      (node (ref "U$17") (pin "4") (pinfunction "C_4") (pintype "bidirectional"))
    )
    (net (code "11") (name "ADC0") (class "Default")
      (node (ref "IC2") (pin "97") (pinfunction "(ADC0)PF0_97") (pintype "bidirectional"))
      (node (ref "JP7") (pin "11") (pinfunction "11_11") (pintype "passive"))
    )
    (net (code "12") (name "ADC1") (class "Default")
      (node (ref "IC2") (pin "96") (pinfunction "(ADC1)PF1_96") (pintype "bidirectional"))
      (node (ref "JP7") (pin "12") (pinfunction "12_12") (pintype "passive"))
    )
    (net (code "13") (name "ADC2") (class "Default")
      (node (ref "IC2") (pin "95") (pinfunction "(ADC2)PF2_95") (pintype "bidirectional"))
      (node (ref "JP7") (pin "13") (pinfunction "13_13") (pintype "passive"))
    )
    (net (code "14") (name "ADC3") (class "Default")
      (node (ref "IC2") (pin "94") (pinfunction "(ADC3)PF3_94") (pintype "bidirectional"))
      (node (ref "JP7") (pin "14") (pinfunction "14_14") (pintype "passive"))
    )
    (net (code "15") (name "ADC4") (class "Default")
      (node (ref "IC2") (pin "93") (pinfunction "(ADC4/TCK)PF4_93") (pintype "bidirectional"))
      (node (ref "JP7") (pin "15") (pinfunction "15_15") (pintype "passive"))
    )
    (net (code "16") (name "ADC5") (class "Default")
      (node (ref "IC2") (pin "92") (pinfunction "(ADC5/TMS)PF5_92") (pintype "bidirectional"))
      (node (ref "JP7") (pin "16") (pinfunction "16_16") (pintype "passive"))
    )
    (net (code "17") (name "ADC6") (class "Default")
      (node (ref "IC2") (pin "91") (pinfunction "(ADC6/TDO)PF6_91") (pintype "bidirectional"))
      (node (ref "JP7") (pin "17") (pinfunction "17_17") (pintype "passive"))
    )
    (net (code "18") (name "ADC7") (class "Default")
      (node (ref "IC2") (pin "90") (pinfunction "(ADC7/TDI)PF7_90") (pintype "bidirectional"))
      (node (ref "JP7") (pin "18") (pinfunction "18_18") (pintype "passive"))
    )
    (net (code "19") (name "ADC8") (class "Default")
      (node (ref "IC2") (pin "89") (pinfunction "PK0(ADC8/PCINT16)_89") (pintype "bidirectional"))
      (node (ref "JP7") (pin "19") (pinfunction "19_19") (pintype "passive"))
    )
    (net (code "20") (name "ADC9") (class "Default")
      (node (ref "IC2") (pin "88") (pinfunction "PK1(ADC9/PCINT17)_88") (pintype "bidirectional"))
      (node (ref "JP7") (pin "20") (pinfunction "20_20") (pintype "passive"))
    )
    (net (code "21") (name "ADC10") (class "Default")
      (node (ref "IC2") (pin "87") (pinfunction "PK2(ADC10/PCINT18)_87") (pintype "bidirectional"))
      (node (ref "JP7") (pin "21") (pinfunction "21_21") (pintype "passive"))
    )
    (net (code "22") (name "ADC11") (class "Default")
      (node (ref "IC2") (pin "86") (pinfunction "PK3(ADC11/PCINT19)_86") (pintype "bidirectional"))
      (node (ref "JP7") (pin "22") (pinfunction "22_22") (pintype "passive"))
    )
    (net (code "23") (name "ADC12") (class "Default")
      (node (ref "IC2") (pin "85") (pinfunction "PK4(ADC12/PCINT20)_85") (pintype "bidirectional"))
      (node (ref "JP7") (pin "23") (pinfunction "23_23") (pintype "passive"))
    )
    (net (code "24") (name "ADC13") (class "Default")
      (node (ref "IC2") (pin "84") (pinfunction "PK5(ADC13/PCINT21)_84") (pintype "bidirectional"))
      (node (ref "JP7") (pin "24") (pinfunction "24_24") (pintype "passive"))
    )
    (net (code "25") (name "ADC14") (class "Default")
      (node (ref "IC2") (pin "83") (pinfunction "PK6(ADC14/PCINT22)_83") (pintype "bidirectional"))
      (node (ref "JP7") (pin "25") (pinfunction "25_25") (pintype "passive"))
    )
    (net (code "26") (name "ADC15") (class "Default")
      (node (ref "IC2") (pin "82") (pinfunction "PK7(ADC15/PCINT23)_82") (pintype "bidirectional"))
      (node (ref "JP7") (pin "26") (pinfunction "26_26") (pintype "passive"))
    )
    (net (code "27") (name "AUTO13") (class "Default")
      (node (ref "JP7") (pin "10") (pinfunction "10_10") (pintype "passive"))
      (node (ref "U5") (pin "5") (pinfunction "IN3_5") (pintype "bidirectional"))
    )
    (net (code "28") (name "D2") (class "Default")
      (node (ref "U3") (pin "32") (pinfunction "PD2(INT0)_32") (pintype "bidirectional"))
    )
    (net (code "29") (name "DBUGRX") (class "Default")
      (node (ref "DEBUG") (pin "2") (pinfunction "2_2") (pintype "passive"))
      (node (ref "U13") (pin "12") (pinfunction "A0_12") (pintype "bidirectional"))
    )
    (net (code "30") (name "DBUGTX") (class "Default")
      (node (ref "DEBUG") (pin "1") (pinfunction "1_1") (pintype "passive"))
      (node (ref "U13") (pin "1") (pinfunction "B0_1") (pintype "bidirectional"))
    )
    (net (code "31") (name "ETHCONECT") (class "Default")
      (node (ref "ELINK") (pin "C") (pinfunction "C_C") (pintype "passive"))
      (node (ref "U1") (pin "18") (pinfunction "ELED1_18") (pintype "bidirectional"))
    )
    (net (code "32") (name "FPIC") (class "Default")
      (node (ref "JP7") (pin "7") (pinfunction "7_7") (pintype "passive"))
      (node (ref "U13") (pin "11") (pinfunction "A3_11") (pintype "bidirectional"))
    )
    (net (code "33") (name "GND") (class "Default")
      (node (ref "13") (pin "C") (pinfunction "C_C") (pintype "passive"))
      (node (ref "5V") (pin "1") (pinfunction "1_1") (pintype "passive"))
      (node (ref "5V-LED") (pin "1") (pinfunction "1_1") (pintype "passive"))
      (node (ref "5V-LED\\") (pin "C") (pinfunction "C_C") (pintype "passive"))
      (node (ref "5V-SEN") (pin "1") (pinfunction "1_1") (pintype "passive"))
      (node (ref "5V-SEN\\") (pin "C") (pinfunction "C_C") (pintype "passive"))
      (node (ref "5V\\") (pin "C") (pinfunction "C_C") (pintype "passive"))
      (node (ref "9V") (pin "1") (pinfunction "1_1") (pintype "passive"))
      (node (ref "9V\\") (pin "C") (pinfunction "C_C") (pintype "passive"))
      (node (ref "C1") (pin "-") (pinfunction "-_-") (pintype "passive"))
      (node (ref "C10") (pin "C") (pinfunction "-_C") (pintype "passive"))
      (node (ref "C16") (pin "2") (pinfunction "2_2") (pintype "passive"))
      (node (ref "C17") (pin "2") (pinfunction "2_2") (pintype "passive"))
      (node (ref "C18") (pin "2") (pinfunction "2_2") (pintype "passive"))
      (node (ref "C19") (pin "2") (pinfunction "2_2") (pintype "passive"))
      (node (ref "C2") (pin "-") (pinfunction "-_-") (pintype "passive"))
      (node (ref "C20") (pin "2") (pinfunction "2_2") (pintype "passive"))
      (node (ref "C3") (pin "-") (pinfunction "-_-") (pintype "passive"))
      (node (ref "C4") (pin "-") (pinfunction "-_-") (pintype "passive"))
      (node (ref "C5") (pin "2") (pinfunction "2_2") (pintype "passive"))
      (node (ref "C6") (pin "2") (pinfunction "2_2") (pintype "passive"))
      (node (ref "C7") (pin "2") (pinfunction "2_2") (pintype "passive"))
      (node (ref "C8") (pin "C") (pinfunction "-_C") (pintype "passive"))
      (node (ref "C9") (pin "1") (pinfunction "1_1") (pintype "passive"))
      (node (ref "CN1") (pin "GND") (pinfunction "GND_GND") (pintype "power_in"))
      (node (ref "DEBUG") (pin "3") (pinfunction "3_3") (pintype "passive"))
      (node (ref "H10") (pin "B2,8") (pinfunction "MOUNT_B2,8") (pintype "passive"))
      (node (ref "H2") (pin "B2,8") (pinfunction "MOUNT_B2,8") (pintype "passive"))
      (node (ref "H4") (pin "B2,8") (pinfunction "MOUNT_B2,8") (pintype "passive"))
      (node (ref "H5") (pin "B2,8") (pinfunction "MOUNT_B2,8") (pintype "passive"))
      (node (ref "H6") (pin "B2,8") (pinfunction "MOUNT_B2,8") (pintype "passive"))
      (node (ref "IC1") (pin "18") (pinfunction "GND_18") (pintype "power_in"))
      (node (ref "IC1") (pin "21") (pinfunction "GND_21") (pintype "power_in"))
      (node (ref "IC1") (pin "25") (pinfunction "GND_25") (pintype "power_in"))
      (node (ref "IC1") (pin "26") (pinfunction "TEST_26") (pintype "input"))
      (node (ref "IC1") (pin "7") (pinfunction "GND_7") (pintype "power_in"))
      (node (ref "IC2") (pin "11") (pinfunction "GND_11") (pintype "power_in"))
      (node (ref "IC2") (pin "32") (pinfunction "GND1_32") (pintype "power_in"))
      (node (ref "IC2") (pin "62") (pinfunction "GND2_62") (pintype "power_in"))
      (node (ref "IC2") (pin "81") (pinfunction "GND3_81") (pintype "power_in"))
      (node (ref "IC2") (pin "99") (pinfunction "AGND_99") (pintype "power_in"))
      (node (ref "ICSP") (pin "6") (pinfunction "6_6") (pintype "passive"))
      (node (ref "ISP2") (pin "6") (pinfunction "GND_6") (pintype "power_in"))
      (node (ref "J1") (pin "4") (pinfunction "4_4") (pintype "passive"))
      (node (ref "J3") (pin "4") (pinfunction "4_4") (pintype "passive"))
      (node (ref "J4") (pin "10") (pinfunction "10_10") (pintype "passive"))
      (node (ref "J4") (pin "6") (pinfunction "6_6") (pintype "passive"))
      (node (ref "J4") (pin "7") (pinfunction "7_7") (pintype "passive"))
      (node (ref "J4") (pin "8") (pinfunction "8_8") (pintype "passive"))
      (node (ref "J4") (pin "9") (pinfunction "9_9") (pintype "passive"))
      (node (ref "J5") (pin "4") (pinfunction "4_4") (pintype "passive"))
      (node (ref "J6") (pin "4") (pinfunction "4_4") (pintype "passive"))
      (node (ref "J7") (pin "4") (pinfunction "4_4") (pintype "passive"))
      (node (ref "J8") (pin "1") (pinfunction "1_1") (pintype "passive"))
      (node (ref "JP1") (pin "3") (pinfunction "3_3") (pintype "passive"))
      (node (ref "JP10") (pin "1") (pinfunction "1_1") (pintype "passive"))
      (node (ref "JP3") (pin "3") (pinfunction "3_3") (pintype "passive"))
      (node (ref "LAN") (pin "1") (pinfunction "1_1") (pintype "passive"))
      (node (ref "LED2") (pin "C") (pinfunction "C_C") (pintype "passive"))
      (node (ref "OSS") (pin "2") (pinfunction "GND_2") (pintype "bidirectional"))
      (node (ref "R24") (pin "2") (pinfunction "2_2") (pintype "passive"))
      (node (ref "R27") (pin "2") (pinfunction "2_2") (pintype "passive"))
      (node (ref "RS485") (pin "3") (pinfunction "3_3") (pintype "passive"))
      (node (ref "S1") (pin "3") (pinfunction "3_3") (pintype "passive"))
      (node (ref "S1") (pin "4") (pinfunction "4_4") (pintype "passive"))
      (node (ref "S2") (pin "1") (pinfunction "1_1") (pintype "passive"))
      (node (ref "S2") (pin "2") (pinfunction "2_2") (pintype "passive"))
      (node (ref "T2") (pin "1") (pinfunction "2_1") (pintype "passive"))
      (node (ref "U$16") (pin "3") (pinfunction "E_3") (pintype "bidirectional"))
      (node (ref "U$17") (pin "3") (pinfunction "E_3") (pintype "bidirectional"))
      (node (ref "U$18") (pin "3") (pinfunction "E_3") (pintype "bidirectional"))
      (node (ref "U$19") (pin "3") (pinfunction "E_3") (pintype "bidirectional"))
      (node (ref "U1") (pin "2") (pinfunction "GND_2") (pintype "bidirectional"))
      (node (ref "U1") (pin "39") (pinfunction "GND_39") (pintype "bidirectional"))
      (node (ref "U10") (pin "1") (pinfunction "RO_1") (pintype "output"))
      (node (ref "U10") (pin "2") (pinfunction "RE/_2") (pintype "input"))
      (node (ref "U10") (pin "3") (pinfunction "DE_3") (pintype "input"))
      (node (ref "U10") (pin "5") (pinfunction "GND_5") (pintype "bidirectional"))
      (node (ref "U11") (pin "1") (pinfunction "RO_1") (pintype "output"))
      (node (ref "U11") (pin "2") (pinfunction "RE/_2") (pintype "input"))
      (node (ref "U11") (pin "3") (pinfunction "DE_3") (pintype "input"))
      (node (ref "U11") (pin "5") (pinfunction "GND_5") (pintype "bidirectional"))
      (node (ref "U12") (pin "3") (pinfunction "GND_3") (pintype "bidirectional"))
      (node (ref "U12") (pin "G") (pinfunction "GND_G") (pintype "bidirectional"))
      (node (ref "U13") (pin "6") (pinfunction "~{E}_6") (pintype "bidirectional"))
      (node (ref "U13") (pin "7") (pinfunction "VEE_7") (pintype "bidirectional"))
      (node (ref "U13") (pin "8") (pinfunction "GND_8") (pintype "bidirectional"))
      (node (ref "U2") (pin "4") (pinfunction "GND_4") (pintype "bidirectional"))
      (node (ref "U4") (pin "5") (pinfunction "GND2_5") (pintype "bidirectional"))
      (node (ref "U5") (pin "2") (pinfunction "GND1_2") (pintype "bidirectional"))
      (node (ref "U5") (pin "8") (pinfunction "GND1_8") (pintype "bidirectional"))
      (node (ref "U6") (pin "21") (pinfunction "GND_21") (pintype "bidirectional"))
      (node (ref "U6") (pin "3") (pinfunction "GND_3") (pintype "bidirectional"))
      (node (ref "U6") (pin "5") (pinfunction "AGND_5") (pintype "bidirectional"))
      (node (ref "U8") (pin "1") (pinfunction "RO_1") (pintype "output"))
      (node (ref "U8") (pin "2") (pinfunction "RE/_2") (pintype "input"))
      (node (ref "U8") (pin "3") (pinfunction "DE_3") (pintype "input"))
      (node (ref "U8") (pin "5") (pinfunction "GND_5") (pintype "bidirectional"))
      (node (ref "U9") (pin "1") (pinfunction "RO_1") (pintype "output"))
      (node (ref "U9") (pin "2") (pinfunction "RE/_2") (pintype "input"))
      (node (ref "U9") (pin "3") (pinfunction "DE_3") (pintype "input"))
      (node (ref "U9") (pin "5") (pinfunction "GND_5") (pintype "bidirectional"))
      (node (ref "UART0") (pin "3") (pinfunction "3_3") (pintype "passive"))
      (node (ref "UART2") (pin "1") (pinfunction "1_1") (pintype "passive"))
      (node (ref "X2") (pin "2") (pinfunction "GND_2") (pintype "bidirectional"))
    )
    (net (code "34") (name "GNDIO") (class "Default")
      (node (ref "C11") (pin "2") (pinfunction "2_2") (pintype "passive"))
      (node (ref "C12") (pin "-") (pinfunction "-_-") (pintype "passive"))
      (node (ref "C13") (pin "-") (pinfunction "-_-") (pintype "passive"))
      (node (ref "C14") (pin "2") (pinfunction "2_2") (pintype "passive"))
      (node (ref "C15") (pin "2") (pinfunction "2_2") (pintype "passive"))
      (node (ref "C23") (pin "-") (pinfunction "-_-") (pintype "passive"))
      (node (ref "C25") (pin "2") (pinfunction "2_2") (pintype "passive"))
      (node (ref "ISP1") (pin "6") (pinfunction "GND_6") (pintype "power_in"))
      (node (ref "JP4") (pin "2") (pinfunction "2_2") (pintype "passive"))
      (node (ref "JP6") (pin "1") (pinfunction "1_1") (pintype "passive"))
      (node (ref "LED1") (pin "C") (pinfunction "C_C") (pintype "passive"))
      (node (ref "R20") (pin "1") (pinfunction "1_1") (pintype "passive"))
      (node (ref "S3") (pin "1") (pinfunction "1_1") (pintype "passive"))
      (node (ref "S3") (pin "2") (pinfunction "2_2") (pintype "passive"))
      (node (ref "T2") (pin "7") (pinfunction "3_7") (pintype "passive"))
      (node (ref "U$16") (pin "2") (pinfunction "K_2") (pintype "bidirectional"))
      (node (ref "U$17") (pin "2") (pinfunction "K_2") (pintype "bidirectional"))
      (node (ref "U$18") (pin "2") (pinfunction "K_2") (pintype "bidirectional"))
      (node (ref "U$19") (pin "2") (pinfunction "K_2") (pintype "bidirectional"))
      (node (ref "U20") (pin "2") (pinfunction "GND_2") (pintype "bidirectional"))
      (node (ref "U3") (pin "21") (pinfunction "GND_21") (pintype "bidirectional"))
      (node (ref "U3") (pin "3") (pinfunction "GND_3") (pintype "bidirectional"))
      (node (ref "U3") (pin "5") (pinfunction "AGND_5") (pintype "bidirectional"))
      (node (ref "U4") (pin "4") (pinfunction "GND1_4") (pintype "bidirectional"))
      (node (ref "U5") (pin "15") (pinfunction "GND2_15") (pintype "bidirectional"))
      (node (ref "U5") (pin "9") (pinfunction "GND2_9") (pintype "bidirectional"))
      (node (ref "U7") (pin "2") (pinfunction "VSS_2") (pintype "power_in"))
      (node (ref "VREG") (pin "2") (pinfunction "GND_2") (pintype "input"))
      (node (ref "X4") (pin "2") (pinfunction "GND_2") (pintype "bidirectional"))
    )
    (net (code "35") (name "LEDRX") (class "Default")
      (node (ref "U13") (pin "15") (pinfunction "A2_15") (pintype "bidirectional"))
      (node (ref "U6") (pin "31") (pinfunction "PD1(TXD)_31") (pintype "bidirectional"))
    )
    (net (code "36") (name "LEDTX") (class "Default")
      (node (ref "U13") (pin "2") (pinfunction "B2_2") (pintype "bidirectional"))
      (node (ref "U6") (pin "30") (pinfunction "PD0(RXD)_30") (pintype "bidirectional"))
    )
    (net (code "37") (name "MCSRX") (class "Default")
      (node (ref "IC2") (pin "63") (pinfunction "PJ0(RXD3/PCINT9)_63") (pintype "bidirectional"))
      (node (ref "RS485") (pin "1") (pinfunction "1_1") (pintype "passive"))
      (node (ref "RX\\") (pin "C") (pinfunction "C_C") (pintype "passive"))
      (node (ref "U2") (pin "2") (pinfunction "RO_2") (pintype "bidirectional"))
    )
    (net (code "38") (name "MCSTX") (class "Default")
      (node (ref "IC2") (pin "64") (pinfunction "PJ1(TXD3/PCINT10)_64") (pintype "bidirectional"))
      (node (ref "RS485") (pin "2") (pinfunction "2_2") (pintype "passive"))
      (node (ref "TX\\") (pin "C") (pinfunction "C_C") (pintype "passive"))
      (node (ref "U2") (pin "3") (pinfunction "DI_3") (pintype "bidirectional"))
    )
    (net (code "39") (name "MISO-1") (class "Default")
      (node (ref "IC2") (pin "22") (pinfunction "(MISO/PCINT3)PB3_22") (pintype "bidirectional"))
      (node (ref "ICSP") (pin "1") (pinfunction "1_1") (pintype "passive"))
    )
    (net (code "40") (name "MOSI-1") (class "Default")
      (node (ref "IC2") (pin "21") (pinfunction "(MOSI/PCINT2)PB2_21") (pintype "bidirectional"))
      (node (ref "ICSP") (pin "4") (pinfunction "4_4") (pintype "passive"))
    )
    (net (code "41") (name "Net-(5V-LED\\-PadA)") (class "Default")
      (node (ref "5V-LED\\") (pin "A") (pinfunction "A_A") (pintype "passive"))
      (node (ref "R21") (pin "2") (pinfunction "2_2") (pintype "passive"))
    )
    (net (code "42") (name "Net-(5V-SEN\\-PadA)") (class "Default")
      (node (ref "5V-SEN\\") (pin "A") (pinfunction "A_A") (pintype "passive"))
      (node (ref "R11") (pin "2") (pinfunction "2_2") (pintype "passive"))
    )
    (net (code "43") (name "Net-(5V\\-PadA)") (class "Default")
      (node (ref "5V\\") (pin "A") (pinfunction "A_A") (pintype "passive"))
      (node (ref "R10") (pin "2") (pinfunction "2_2") (pintype "passive"))
    )
    (net (code "44") (name "Net-(9V\\-PadA)") (class "Default")
      (node (ref "9V\\") (pin "A") (pinfunction "A_A") (pintype "passive"))
      (node (ref "R12") (pin "2") (pinfunction "2_2") (pintype "passive"))
    )
    (net (code "45") (name "Net-(13-PadA)") (class "Default")
      (node (ref "13") (pin "A") (pinfunction "A_A") (pintype "passive"))
      (node (ref "R25") (pin "2") (pinfunction "2_2") (pintype "passive"))
    )
    (net (code "46") (name "Net-(C9-Pad2)") (class "Default")
      (node (ref "C9") (pin "2") (pinfunction "2_2") (pintype "passive"))
      (node (ref "R8") (pin "2") (pinfunction "2_2") (pintype "passive"))
      (node (ref "R9") (pin "2") (pinfunction "2_2") (pintype "passive"))
      (node (ref "X1") (pin "10") (pinfunction "10_10") (pintype "bidirectional"))
      (node (ref "X1") (pin "15") (pinfunction "15_15") (pintype "bidirectional"))
    )
    (net (code "47") (name "Net-(CG-PadC)") (class "Default")
      (node (ref "CG") (pin "C") (pinfunction "C_C") (pintype "passive"))
      (node (ref "R16") (pin "1") (pinfunction "1_1") (pintype "passive"))
    )
    (net (code "48") (name "Net-(CHG-S)") (class "Default")
      (node (ref "CHG") (pin "3") (pinfunction "S_3") (pintype "passive"))
      (node (ref "T2") (pin "3") (pinfunction "1_3") (pintype "passive"))
    )
    (net (code "49") (name "Net-(EACT-PadA)") (class "Default")
      (node (ref "EACT") (pin "A") (pinfunction "A_A") (pintype "passive"))
      (node (ref "R6") (pin "2") (pinfunction "2_2") (pintype "passive"))
    )
    (net (code "50") (name "Net-(ELINK-PadA)") (class "Default")
      (node (ref "ELINK") (pin "A") (pinfunction "A_A") (pintype "passive"))
      (node (ref "R7") (pin "2") (pinfunction "2_2") (pintype "passive"))
    )
    (net (code "51") (name "Net-(IC1-3V3OUT)") (class "Default")
      (node (ref "C6") (pin "1") (pinfunction "1_1") (pintype "passive"))
      (node (ref "IC1") (pin "17") (pinfunction "3V3OUT_17") (pintype "output"))
      (node (ref "IC1") (pin "4") (pinfunction "VCCIO_4") (pintype "power_in"))
    )
    (net (code "52") (name "Net-(IC1-CBUS0)") (class "Default")
      (node (ref "IC1") (pin "23") (pinfunction "CBUS0_23") (pintype "bidirectional"))
      (node (ref "TX") (pin "C") (pinfunction "C_C") (pintype "passive"))
    )
    (net (code "53") (name "Net-(IC1-CBUS1)") (class "Default")
      (node (ref "IC1") (pin "22") (pinfunction "CBUS1_22") (pintype "bidirectional"))
      (node (ref "RX") (pin "C") (pinfunction "C_C") (pintype "passive"))
    )
    (net (code "54") (name "Net-(IC1-RXD)") (class "Default")
      (node (ref "IC1") (pin "5") (pinfunction "RXD_5") (pintype "input"))
      (node (ref "JP1") (pin "2") (pinfunction "2_2") (pintype "passive"))
    )
    (net (code "55") (name "Net-(IC1-TXD)") (class "Default")
      (node (ref "IC1") (pin "1") (pinfunction "TXD_1") (pintype "output"))
      (node (ref "JP1") (pin "1") (pinfunction "1_1") (pintype "passive"))
    )
    (net (code "56") (name "Net-(IC1-USBDM)") (class "Default")
      (node (ref "CN1") (pin "D-") (pinfunction "D-_D-") (pintype "bidirectional"))
      (node (ref "IC1") (pin "16") (pinfunction "USBDM_16") (pintype "bidirectional"))
      (node (ref "JP10") (pin "3") (pinfunction "3_3") (pintype "passive"))
    )
    (net (code "57") (name "Net-(IC1-USBDP)") (class "Default")
      (node (ref "CN1") (pin "D+") (pinfunction "D+_D+") (pintype "bidirectional"))
      (node (ref "IC1") (pin "15") (pinfunction "USBDP_15") (pintype "bidirectional"))
      (node (ref "JP10") (pin "2") (pinfunction "2_2") (pintype "passive"))
    )
    (net (code "58") (name "Net-(IC2-XTAL1)") (class "Default")
      (node (ref "IC2") (pin "34") (pinfunction "XTAL1_34") (pintype "input"))
      (node (ref "OSS") (pin "3") (pinfunction "OUT_3") (pintype "bidirectional"))
    )
    (net (code "59") (name "Net-(IC2-XTAL2)") (class "Default")
      (node (ref "IC2") (pin "33") (pinfunction "XTAL2_33") (pintype "output"))
      (node (ref "OSS") (pin "1") (pinfunction "IN_1") (pintype "bidirectional"))
    )
    (net (code "60") (name "Net-(ISP1-MOSI)") (class "Default")
      (node (ref "ISP1") (pin "4") (pinfunction "MOSI_4") (pintype "output"))
      (node (ref "U3") (pin "15") (pinfunction "PB3(MOSI/OC2)_15") (pintype "bidirectional"))
    )
    (net (code "61") (name "Net-(ISP1-SCK)") (class "Default")
      (node (ref "ISP1") (pin "3") (pinfunction "SCK_3") (pintype "output"))
      (node (ref "R14") (pin "1") (pinfunction "1_1") (pintype "passive"))
      (node (ref "U3") (pin "17") (pinfunction "PB5(SCK)_17") (pintype "bidirectional"))
    )
    (net (code "62") (name "Net-(ISP2-MISO)") (class "Default")
      (node (ref "ISP2") (pin "1") (pinfunction "MISO_1") (pintype "input"))
      (node (ref "U6") (pin "16") (pinfunction "PB4(MISO)_16") (pintype "bidirectional"))
    )
    (net (code "63") (name "Net-(ISP2-MOSI)") (class "Default")
      (node (ref "ISP2") (pin "4") (pinfunction "MOSI_4") (pintype "output"))
      (node (ref "U6") (pin "15") (pinfunction "PB3(MOSI/OC2)_15") (pintype "bidirectional"))
    )
    (net (code "64") (name "Net-(ISP2-SCK)") (class "Default")
      (node (ref "ISP2") (pin "3") (pinfunction "SCK_3") (pintype "output"))
      (node (ref "R17") (pin "1") (pinfunction "1_1") (pintype "passive"))
      (node (ref "U6") (pin "17") (pinfunction "PB5(SCK)_17") (pintype "bidirectional"))
    )
    (net (code "65") (name "Net-(JP2-Pad1)") (class "Default")
      (node (ref "JP2") (pin "1") (pinfunction "1_1") (pintype "passive"))
      (node (ref "X1") (pin "16") (pinfunction "16_16") (pintype "bidirectional"))
    )
    (net (code "66") (name "Net-(JP2-Pad2)") (class "Default")
      (node (ref "JP2") (pin "2") (pinfunction "2_2") (pintype "passive"))
      (node (ref "X1") (pin "14") (pinfunction "14_14") (pintype "bidirectional"))
    )
    (net (code "67") (name "Net-(JP2-Pad3)") (class "Default")
      (node (ref "JP2") (pin "3") (pinfunction "3_3") (pintype "passive"))
      (node (ref "X1") (pin "11") (pinfunction "11_11") (pintype "bidirectional"))
    )
    (net (code "68") (name "Net-(JP2-Pad4)") (class "Default")
      (node (ref "JP2") (pin "4") (pinfunction "4_4") (pintype "passive"))
      (node (ref "JP2") (pin "5") (pinfunction "5_5") (pintype "passive"))
      (node (ref "R9") (pin "1") (pinfunction "1_1") (pintype "passive"))
    )
    (net (code "69") (name "Net-(JP2-Pad6)") (class "Default")
      (node (ref "JP2") (pin "6") (pinfunction "6_6") (pintype "passive"))
      (node (ref "X1") (pin "9") (pinfunction "9_9") (pintype "bidirectional"))
    )
    (net (code "70") (name "Net-(JP2-Pad7)") (class "Default")
      (node (ref "JP2") (pin "7") (pinfunction "7_7") (pintype "passive"))
      (node (ref "JP2") (pin "8") (pinfunction "8_8") (pintype "passive"))
      (node (ref "R8") (pin "1") (pinfunction "1_1") (pintype "passive"))
    )
    (net (code "71") (name "Net-(JP12-Pad1)") (class "Default")
      (node (ref "JP12") (pin "1") (pinfunction "1_1") (pintype "passive"))
      (node (ref "K1") (pin "5") (pinfunction "5_5") (pintype "passive"))
    )
    (net (code "72") (name "Net-(JP12-Pad2)") (class "Default")
      (node (ref "JP12") (pin "2") (pinfunction "2_2") (pintype "passive"))
      (node (ref "K1") (pin "3") (pinfunction "3_3") (pintype "passive"))
    )
    (net (code "73") (name "Net-(K1B-P)") (class "Default")
      (node (ref "JP6") (pin "2") (pinfunction "2_2") (pintype "passive"))
      (node (ref "K1") (pin "1") (pinfunction "P_1") (pintype "passive"))
    )
    (net (code "74") (name "Net-(LED1-PadA)") (class "Default")
      (node (ref "LED1") (pin "A") (pinfunction "A_A") (pintype "passive"))
      (node (ref "R14") (pin "2") (pinfunction "2_2") (pintype "passive"))
    )
    (net (code "75") (name "Net-(LED2-PadA)") (class "Default")
      (node (ref "LED2") (pin "A") (pinfunction "A_A") (pintype "passive"))
      (node (ref "R17") (pin "2") (pinfunction "2_2") (pintype "passive"))
    )
    (net (code "76") (name "Net-(LED3-PadA)") (class "Default")
      (node (ref "LED3") (pin "A") (pinfunction "A_A") (pintype "passive"))
      (node (ref "R34") (pin "1") (pinfunction "1_1") (pintype "passive"))
    )
    (net (code "77") (name "Net-(LED4-PadA)") (class "Default")
      (node (ref "LED4") (pin "A") (pinfunction "A_A") (pintype "passive"))
      (node (ref "R35") (pin "1") (pinfunction "1_1") (pintype "passive"))
    )
    (net (code "78") (name "Net-(LED5-PadA)") (class "Default")
      (node (ref "LED5") (pin "A") (pinfunction "A_A") (pintype "passive"))
      (node (ref "R36") (pin "1") (pinfunction "1_1") (pintype "passive"))
    )
    (net (code "79") (name "Net-(LED6-PadA)") (class "Default")
      (node (ref "LED6") (pin "A") (pinfunction "A_A") (pintype "passive"))
      (node (ref "R37") (pin "1") (pinfunction "1_1") (pintype "passive"))
    )
    (net (code "80") (name "Net-(LED7-PadA)") (class "Default")
      (node (ref "LED7") (pin "A") (pinfunction "A_A") (pintype "passive"))
      (node (ref "R28") (pin "1") (pinfunction "1_1") (pintype "passive"))
    )
    (net (code "81") (name "Net-(LED8-PadA)") (class "Default")
      (node (ref "LED8") (pin "A") (pinfunction "A_A") (pintype "passive"))
      (node (ref "R29") (pin "1") (pinfunction "1_1") (pintype "passive"))
    )
    (net (code "82") (name "Net-(R2-Pad1)") (class "Default")
      (node (ref "R2") (pin "1") (pinfunction "1_1") (pintype "passive"))
      (node (ref "RX\\") (pin "A") (pinfunction "A_A") (pintype "passive"))
    )
    (net (code "83") (name "Net-(R3-Pad2)") (class "Default")
      (node (ref "R3") (pin "2") (pinfunction "2_2") (pintype "passive"))
      (node (ref "RX") (pin "A") (pinfunction "A_A") (pintype "passive"))
    )
    (net (code "84") (name "Net-(R4-Pad2)") (class "Default")
      (node (ref "R4") (pin "2") (pinfunction "2_2") (pintype "passive"))
      (node (ref "TX") (pin "A") (pinfunction "A_A") (pintype "passive"))
    )
    (net (code "85") (name "Net-(R5-Pad2)") (class "Default")
      (node (ref "R5") (pin "2") (pinfunction "2_2") (pintype "passive"))
      (node (ref "WIFI") (pin "A") (pinfunction "A_A") (pintype "passive"))
    )
    (net (code "86") (name "Net-(R18-Pad1)") (class "Default")
      (node (ref "R18") (pin "1") (pinfunction "1_1") (pintype "passive"))
      (node (ref "TX\\") (pin "A") (pinfunction "A_A") (pintype "passive"))
    )
    (net (code "87") (name "Net-(T2-4)") (class "Default")
      (node (ref "L2") (pin "2") (pinfunction "2_2") (pintype "passive"))
      (node (ref "T2") (pin "8") (pinfunction "4_8") (pintype "passive"))
    )
    (net (code "88") (name "Net-(U$16-A)") (class "Default")
      (node (ref "R45") (pin "1") (pinfunction "1_1") (pintype "passive"))
      (node (ref "U$16") (pin "1") (pinfunction "A_1") (pintype "bidirectional"))
    )
    (net (code "89") (name "Net-(U$17-A)") (class "Default")
      (node (ref "R47") (pin "1") (pinfunction "1_1") (pintype "passive"))
      (node (ref "U$17") (pin "1") (pinfunction "A_1") (pintype "bidirectional"))
    )
    (net (code "90") (name "Net-(U$18-A)") (class "Default")
      (node (ref "R44") (pin "1") (pinfunction "1_1") (pintype "passive"))
      (node (ref "U$18") (pin "1") (pinfunction "A_1") (pintype "bidirectional"))
    )
    (net (code "91") (name "Net-(U$19-A)") (class "Default")
      (node (ref "R46") (pin "1") (pinfunction "1_1") (pintype "passive"))
      (node (ref "U$19") (pin "1") (pinfunction "A_1") (pintype "bidirectional"))
    )
    (net (code "92") (name "Net-(U1-ELED2)") (class "Default")
      (node (ref "EACT") (pin "C") (pinfunction "C_C") (pintype "passive"))
      (node (ref "U1") (pin "20") (pinfunction "ELED2_20") (pintype "bidirectional"))
    )
    (net (code "93") (name "Net-(U1-RX+)") (class "Default")
      (node (ref "U1") (pin "14") (pinfunction "RX+_14") (pintype "bidirectional"))
      (node (ref "X1") (pin "6") (pinfunction "6_6") (pintype "bidirectional"))
    )
    (net (code "94") (name "Net-(U1-RX-)") (class "Default")
      (node (ref "U1") (pin "16") (pinfunction "RX-_16") (pintype "bidirectional"))
      (node (ref "X1") (pin "8") (pinfunction "8_8") (pintype "bidirectional"))
    )
    (net (code "95") (name "Net-(U1-RXCT)") (class "Default")
      (node (ref "U1") (pin "12") (pinfunction "RXCT_12") (pintype "bidirectional"))
      (node (ref "X1") (pin "7") (pinfunction "7_7") (pintype "bidirectional"))
    )
    (net (code "96") (name "Net-(U1-TX+)") (class "Default")
      (node (ref "U1") (pin "6") (pinfunction "TX+_6") (pintype "bidirectional"))
      (node (ref "X1") (pin "1") (pinfunction "1_1") (pintype "bidirectional"))
    )
    (net (code "97") (name "Net-(U1-TX-)") (class "Default")
      (node (ref "U1") (pin "8") (pinfunction "TX-_8") (pintype "bidirectional"))
      (node (ref "X1") (pin "3") (pinfunction "3_3") (pintype "bidirectional"))
    )
    (net (code "98") (name "Net-(U1-TXCT)") (class "Default")
      (node (ref "U1") (pin "10") (pinfunction "TXCT_10") (pintype "bidirectional"))
      (node (ref "X1") (pin "2") (pinfunction "2_2") (pintype "bidirectional"))
    )
    (net (code "99") (name "Net-(U3-PB6(XTAL1{slash}TOSC1))") (class "Default")
      (node (ref "U3") (pin "7") (pinfunction "PB6(XTAL1/TOSC1)_7") (pintype "bidirectional"))
      (node (ref "X4") (pin "1") (pinfunction "IN_1") (pintype "bidirectional"))
    )
    (net (code "100") (name "Net-(U3-PB7(XTAL2{slash}TOSC2))") (class "Default")
      (node (ref "U3") (pin "8") (pinfunction "PB7(XTAL2/TOSC2)_8") (pintype "bidirectional"))
      (node (ref "X4") (pin "3") (pinfunction "OUT_3") (pintype "bidirectional"))
    )
    (net (code "101") (name "Net-(U3-PC0(ADC0))") (class "Default")
      (node (ref "R45") (pin "2") (pinfunction "2_2") (pintype "passive"))
      (node (ref "U3") (pin "23") (pinfunction "PC0(ADC0)_23") (pintype "bidirectional"))
    )
    (net (code "102") (name "Net-(U3-PC1(ADC1))") (class "Default")
      (node (ref "R46") (pin "2") (pinfunction "2_2") (pintype "passive"))
      (node (ref "U3") (pin "24") (pinfunction "PC1(ADC1)_24") (pintype "bidirectional"))
    )
    (net (code "103") (name "Net-(U3-PC2(ADC2))") (class "Default")
      (node (ref "R44") (pin "2") (pinfunction "2_2") (pintype "passive"))
      (node (ref "U3") (pin "25") (pinfunction "PC2(ADC2)_25") (pintype "bidirectional"))
    )
    (net (code "104") (name "Net-(U3-PC3(ADC3))") (class "Default")
      (node (ref "R47") (pin "2") (pinfunction "2_2") (pintype "passive"))
      (node (ref "U3") (pin "26") (pinfunction "PC3(ADC3)_26") (pintype "bidirectional"))
    )
    (net (code "105") (name "Net-(U3-PD0(RXD))") (class "Default")
      (node (ref "U3") (pin "30") (pinfunction "PD0(RXD)_30") (pintype "bidirectional"))
      (node (ref "U4") (pin "2") (pinfunction "OUTA_2") (pintype "bidirectional"))
    )
    (net (code "106") (name "Net-(U3-PD1(TXD))") (class "Default")
      (node (ref "U3") (pin "31") (pinfunction "PD1(TXD)_31") (pintype "bidirectional"))
      (node (ref "U4") (pin "3") (pinfunction "INB_3") (pintype "bidirectional"))
    )
    (net (code "107") (name "Net-(U3-PD3(INT1))") (class "Default")
      (node (ref "U3") (pin "1") (pinfunction "PD3(INT1)_1") (pintype "bidirectional"))
      (node (ref "U5") (pin "11") (pinfunction "OUT4_11") (pintype "bidirectional"))
    )
    (net (code "108") (name "Net-(U3-PD4(XCK{slash}T0))") (class "Default")
      (node (ref "U3") (pin "2") (pinfunction "PD4(XCK/T0)_2") (pintype "bidirectional"))
      (node (ref "U5") (pin "12") (pinfunction "OUT3_12") (pintype "bidirectional"))
    )
    (net (code "109") (name "Net-(U3-PD5(T1))") (class "Default")
      (node (ref "U3") (pin "9") (pinfunction "PD5(T1)_9") (pintype "bidirectional"))
      (node (ref "U5") (pin "13") (pinfunction "OUT2_13") (pintype "bidirectional"))
    )
    (net (code "110") (name "Net-(U3-PD6(AIN0))") (class "Default")
      (node (ref "U3") (pin "10") (pinfunction "PD6(AIN0)_10") (pintype "bidirectional"))
      (node (ref "U5") (pin "14") (pinfunction "OUT1_14") (pintype "bidirectional"))
    )
    (net (code "111") (name "Net-(U6-PB6(XTAL1{slash}TOSC1))") (class "Default")
      (node (ref "U6") (pin "7") (pinfunction "PB6(XTAL1/TOSC1)_7") (pintype "bidirectional"))
      (node (ref "X2") (pin "1") (pinfunction "IN_1") (pintype "bidirectional"))
    )
    (net (code "112") (name "Net-(U6-PB7(XTAL2{slash}TOSC2))") (class "Default")
      (node (ref "U6") (pin "8") (pinfunction "PB7(XTAL2/TOSC2)_8") (pintype "bidirectional"))
      (node (ref "X2") (pin "3") (pinfunction "OUT_3") (pintype "bidirectional"))
    )
    (net (code "113") (name "Net-(U6-PD2(INT0))") (class "Default")
      (node (ref "U6") (pin "32") (pinfunction "PD2(INT0)_32") (pintype "bidirectional"))
      (node (ref "U8") (pin "4") (pinfunction "DI_4") (pintype "input"))
    )
    (net (code "114") (name "Net-(U6-PD3(INT1))") (class "Default")
      (node (ref "U6") (pin "1") (pinfunction "PD3(INT1)_1") (pintype "bidirectional"))
      (node (ref "U9") (pin "4") (pinfunction "DI_4") (pintype "input"))
    )
    (net (code "115") (name "Net-(U7-PROG)") (class "Default")
      (node (ref "R20") (pin "2") (pinfunction "2_2") (pintype "passive"))
      (node (ref "U7") (pin "5") (pinfunction "PROG_5") (pintype "input"))
    )
    (net (code "116") (name "Net-(U7-STAT)") (class "Default")
      (node (ref "R16") (pin "2") (pinfunction "2_2") (pintype "passive"))
      (node (ref "U7") (pin "1") (pinfunction "STAT_1") (pintype "output"))
    )
    (net (code "117") (name "Net-(U8-A)") (class "Default")
      (node (ref "J3") (pin "3") (pinfunction "3_3") (pintype "passive"))
      (node (ref "R1") (pin "1") (pinfunction "1_1") (pintype "passive"))
      (node (ref "U8") (pin "6") (pinfunction "A_6") (pintype "passive"))
    )
    (net (code "118") (name "Net-(U8-B)") (class "Default")
      (node (ref "J3") (pin "2") (pinfunction "2_2") (pintype "passive"))
      (node (ref "R1") (pin "2") (pinfunction "2_2") (pintype "passive"))
      (node (ref "U8") (pin "7") (pinfunction "B_7") (pintype "passive"))
    )
    (net (code "119") (name "Net-(U9-A)") (class "Default")
      (node (ref "J5") (pin "3") (pinfunction "3_3") (pintype "passive"))
      (node (ref "R19") (pin "1") (pinfunction "1_1") (pintype "passive"))
      (node (ref "U9") (pin "6") (pinfunction "A_6") (pintype "passive"))
    )
    (net (code "120") (name "Net-(U9-B)") (class "Default")
      (node (ref "J5") (pin "2") (pinfunction "2_2") (pintype "passive"))
      (node (ref "R19") (pin "2") (pinfunction "2_2") (pintype "passive"))
      (node (ref "U9") (pin "7") (pinfunction "B_7") (pintype "passive"))
    )
    (net (code "121") (name "Net-(U10-A)") (class "Default")
      (node (ref "J6") (pin "3") (pinfunction "3_3") (pintype "passive"))
      (node (ref "R22") (pin "1") (pinfunction "1_1") (pintype "passive"))
      (node (ref "U10") (pin "6") (pinfunction "A_6") (pintype "passive"))
    )
    (net (code "122") (name "Net-(U10-B)") (class "Default")
      (node (ref "J6") (pin "2") (pinfunction "2_2") (pintype "passive"))
      (node (ref "R22") (pin "2") (pinfunction "2_2") (pintype "passive"))
      (node (ref "U10") (pin "7") (pinfunction "B_7") (pintype "passive"))
    )
    (net (code "123") (name "Net-(U10-DI)") (class "Default")
      (node (ref "U10") (pin "4") (pinfunction "DI_4") (pintype "input"))
      (node (ref "U6") (pin "2") (pinfunction "PD4(XCK/T0)_2") (pintype "bidirectional"))
    )
    (net (code "124") (name "Net-(U11-A)") (class "Default")
      (node (ref "J7") (pin "3") (pinfunction "3_3") (pintype "passive"))
      (node (ref "R23") (pin "1") (pinfunction "1_1") (pintype "passive"))
      (node (ref "U11") (pin "6") (pinfunction "A_6") (pintype "passive"))
    )
    (net (code "125") (name "Net-(U11-B)") (class "Default")
      (node (ref "J7") (pin "2") (pinfunction "2_2") (pintype "passive"))
      (node (ref "R23") (pin "2") (pinfunction "2_2") (pintype "passive"))
      (node (ref "U11") (pin "7") (pinfunction "B_7") (pintype "passive"))
    )
    (net (code "126") (name "Net-(U11-DI)") (class "Default")
      (node (ref "U11") (pin "4") (pinfunction "DI_4") (pintype "input"))
      (node (ref "U6") (pin "9") (pinfunction "PD5(T1)_9") (pintype "bidirectional"))
    )
    (net (code "127") (name "Net-(U20-~{RST})") (class "Default")
      (node (ref "JP5") (pin "1") (pinfunction "1_1") (pintype "passive"))
      (node (ref "U20") (pin "1") (pinfunction "~{RST}_1") (pintype "bidirectional"))
    )
    (net (code "128") (name "O9") (class "Default")
      (node (ref "IC2") (pin "53") (pinfunction "(A8)PC0_53") (pintype "bidirectional"))
    )
    (net (code "129") (name "O10") (class "Default")
      (node (ref "IC2") (pin "54") (pinfunction "(A9)PC1_54") (pintype "bidirectional"))
    )
    (net (code "130") (name "O11") (class "Default")
      (node (ref "IC2") (pin "55") (pinfunction "(A10)PC2_55") (pintype "bidirectional"))
    )
    (net (code "131") (name "O12") (class "Default")
      (node (ref "IC2") (pin "56") (pinfunction "(A11)PC3_56") (pintype "bidirectional"))
    )
    (net (code "132") (name "O13") (class "Default")
      (node (ref "IC2") (pin "57") (pinfunction "(A12)PC4_57") (pintype "bidirectional"))
    )
    (net (code "133") (name "O14") (class "Default")
      (node (ref "IC2") (pin "58") (pinfunction "(A13)PC5_58") (pintype "bidirectional"))
    )
    (net (code "134") (name "O15") (class "Default")
      (node (ref "IC2") (pin "59") (pinfunction "(A14)PC6_59") (pintype "bidirectional"))
    )
    (net (code "135") (name "O16") (class "Default")
      (node (ref "IC2") (pin "60") (pinfunction "(A15)PC7_60") (pintype "bidirectional"))
    )
    (net (code "136") (name "PIC13") (class "Default")
      (node (ref "JP7") (pin "9") (pinfunction "9_9") (pintype "passive"))
      (node (ref "U5") (pin "6") (pinfunction "IN4_6") (pintype "bidirectional"))
    )
    (net (code "137") (name "PN13") (class "Default")
      (node (ref "IC2") (pin "26") (pinfunction "(OC0A/OC1C/PCINT7)PB7_26") (pintype "bidirectional"))
      (node (ref "R25") (pin "1") (pinfunction "1_1") (pintype "passive"))
      (node (ref "U5") (pin "3") (pinfunction "IN1_3") (pintype "bidirectional"))
    )
    (net (code "138") (name "RSA") (class "Default")
      (node (ref "JP7") (pin "2") (pinfunction "2_2") (pintype "passive"))
      (node (ref "U2") (pin "8") (pinfunction "A_8") (pintype "bidirectional"))
    )
    (net (code "139") (name "RSB") (class "Default")
      (node (ref "JP7") (pin "4") (pinfunction "4_4") (pintype "passive"))
      (node (ref "U2") (pin "7") (pinfunction "B_7") (pintype "bidirectional"))
    )
    (net (code "140") (name "RSY") (class "Default")
      (node (ref "JP7") (pin "8") (pinfunction "8_8") (pintype "passive"))
      (node (ref "U2") (pin "5") (pinfunction "Y_5") (pintype "bidirectional"))
    )
    (net (code "141") (name "RSZ") (class "Default")
      (node (ref "JP7") (pin "6") (pinfunction "6_6") (pintype "passive"))
      (node (ref "U2") (pin "6") (pinfunction "Z_6") (pintype "bidirectional"))
    )
    (net (code "142") (name "RX2") (class "Default")
      (node (ref "IC2") (pin "12") (pinfunction "PH0(RXD2)_12") (pintype "bidirectional"))
      (node (ref "LED3") (pin "C") (pinfunction "C_C") (pintype "passive"))
      (node (ref "U13") (pin "13") (pinfunction "A_13") (pintype "bidirectional"))
      (node (ref "UART2") (pin "2") (pinfunction "2_2") (pintype "passive"))
    )
    (net (code "143") (name "RXD0") (class "Default")
      (node (ref "IC2") (pin "3") (pinfunction "(TXD0)PE1_3") (pintype "bidirectional"))
      (node (ref "JP7") (pin "3") (pinfunction "3_3") (pintype "passive"))
      (node (ref "LED8") (pin "C") (pinfunction "C_C") (pintype "passive"))
      (node (ref "UART0") (pin "1") (pinfunction "1_1") (pintype "passive"))
    )
    (net (code "144") (name "RXD1") (class "Default")
      (node (ref "IC2") (pin "45") (pinfunction "(RXD1/INT2)PD2_45") (pintype "bidirectional"))
      (node (ref "LAN") (pin "2") (pinfunction "2_2") (pintype "passive"))
      (node (ref "LED5") (pin "C") (pinfunction "C_C") (pintype "passive"))
      (node (ref "U1") (pin "5") (pinfunction "TX1_5") (pintype "bidirectional"))
    )
    (net (code "145") (name "S0") (class "Default")
      (node (ref "IC2") (pin "77") (pinfunction "(AD1)PA1_77") (pintype "bidirectional"))
      (node (ref "R27") (pin "1") (pinfunction "1_1") (pintype "passive"))
      (node (ref "U13") (pin "10") (pinfunction "S0_10") (pintype "bidirectional"))
    )
    (net (code "146") (name "S1") (class "Default")
      (node (ref "IC2") (pin "78") (pinfunction "(AD0)PA0_78") (pintype "bidirectional"))
      (node (ref "R24") (pin "1") (pinfunction "1_1") (pintype "passive"))
      (node (ref "U13") (pin "9") (pinfunction "S1_9") (pintype "bidirectional"))
    )
    (net (code "147") (name "SCK-1") (class "Default")
      (node (ref "IC2") (pin "20") (pinfunction "(SCK/PCINT1)PB1_20") (pintype "bidirectional"))
      (node (ref "ICSP") (pin "3") (pinfunction "3_3") (pintype "passive"))
    )
    (net (code "148") (name "SCL") (class "Default")
      (node (ref "IC2") (pin "43") (pinfunction "(SCL/INT0)PD0_43") (pintype "bidirectional"))
      (node (ref "J8") (pin "2") (pinfunction "2_2") (pintype "passive"))
      (node (ref "JP3") (pin "1") (pinfunction "1_1") (pintype "passive"))
      (node (ref "R40") (pin "2") (pinfunction "2_2") (pintype "passive"))
    )
    (net (code "149") (name "SDA") (class "Default")
      (node (ref "IC2") (pin "44") (pinfunction "(SDA/INT1)PD1_44") (pintype "bidirectional"))
      (node (ref "J8") (pin "3") (pinfunction "3_3") (pintype "passive"))
      (node (ref "JP3") (pin "2") (pinfunction "2_2") (pintype "passive"))
      (node (ref "R41") (pin "2") (pinfunction "2_2") (pintype "passive"))
    )
    (net (code "150") (name "TX2") (class "Default")
      (node (ref "IC2") (pin "13") (pinfunction "PH1(TXD2)_13") (pintype "bidirectional"))
      (node (ref "LED4") (pin "C") (pinfunction "C_C") (pintype "passive"))
      (node (ref "U13") (pin "3") (pinfunction "B_3") (pintype "bidirectional"))
      (node (ref "UART2") (pin "3") (pinfunction "3_3") (pintype "passive"))
    )
    (net (code "151") (name "TXD0") (class "Default")
      (node (ref "IC2") (pin "2") (pinfunction "(RXD0/PCIN8)PE0_2") (pintype "bidirectional"))
      (node (ref "JP7") (pin "5") (pinfunction "5_5") (pintype "passive"))
      (node (ref "LED7") (pin "C") (pinfunction "C_C") (pintype "passive"))
      (node (ref "UART0") (pin "2") (pinfunction "2_2") (pintype "passive"))
    )
    (net (code "152") (name "TXD1") (class "Default")
      (node (ref "IC2") (pin "46") (pinfunction "(TXD1/INT3)PD3_46") (pintype "bidirectional"))
      (node (ref "LAN") (pin "3") (pinfunction "3_3") (pintype "passive"))
      (node (ref "LED6") (pin "C") (pinfunction "C_C") (pintype "passive"))
      (node (ref "U1") (pin "9") (pinfunction "RX1_9") (pintype "bidirectional"))
    )
    (net (code "153") (name "USBPR") (class "Default")
      (node (ref "C10") (pin "A") (pinfunction "+_A") (pintype "passive"))
      (node (ref "C5") (pin "1") (pinfunction "1_1") (pintype "passive"))
      (node (ref "CN1") (pin "VBUS") (pinfunction "VBUS_VBUS") (pintype "power_in"))
      (node (ref "IC1") (pin "20") (pinfunction "VCC_20") (pintype "power_in"))
      (node (ref "JP10") (pin "4") (pinfunction "4_4") (pintype "passive"))
      (node (ref "R3") (pin "1") (pinfunction "1_1") (pintype "passive"))
      (node (ref "R4") (pin "1") (pinfunction "1_1") (pintype "passive"))
    )
    (net (code "154") (name "V+") (class "Default")
      (node (ref "C12") (pin "+") (pinfunction "+_+") (pintype "passive"))
      (node (ref "C13") (pin "+") (pinfunction "+_+") (pintype "passive"))
      (node (ref "C14") (pin "1") (pinfunction "1_1") (pintype "passive"))
      (node (ref "C15") (pin "1") (pinfunction "1_1") (pintype "passive"))
      (node (ref "C23") (pin "+") (pinfunction "+_+") (pintype "passive"))
      (node (ref "ISP1") (pin "2") (pinfunction "VCC_2") (pintype "power_in"))
      (node (ref "R13") (pin "2") (pinfunction "2_2") (pintype "passive"))
      (node (ref "U20") (pin "5") (pinfunction "VCC_5") (pintype "bidirectional"))
      (node (ref "U3") (pin "18") (pinfunction "AVCC_18") (pintype "bidirectional"))
      (node (ref "U3") (pin "4") (pinfunction "VCC_4") (pintype "bidirectional"))
      (node (ref "U3") (pin "6") (pinfunction "VCC_6") (pintype "bidirectional"))
      (node (ref "U4") (pin "1") (pinfunction "VCC1_1") (pintype "bidirectional"))
      (node (ref "U5") (pin "16") (pinfunction "VDD2_16") (pintype "bidirectional"))
      (node (ref "VREG") (pin "5") (pinfunction "OUT_5") (pintype "passive"))
    )
    (net (code "155") (name "VBATT") (class "Default")
      (node (ref "K1") (pin "7") (pinfunction "S_7") (pintype "passive"))
      (node (ref "U7") (pin "3") (pinfunction "VBAT_3") (pintype "power_in"))
      (node (ref "VREG") (pin "1") (pinfunction "IN_1") (pintype "input"))
      (node (ref "VREG") (pin "3") (pinfunction "EN_3") (pintype "input"))
    )
    (net (code "156") (name "VBUS") (class "Default")
      (node (ref "C11") (pin "1") (pinfunction "1_1") (pintype "passive"))
      (node (ref "C25") (pin "1") (pinfunction "1_1") (pintype "passive"))
      (node (ref "CG") (pin "A") (pinfunction "A_A") (pintype "passive"))
      (node (ref "JP4") (pin "1") (pinfunction "1_1") (pintype "passive"))
      (node (ref "L2") (pin "1") (pinfunction "1_1") (pintype "passive"))
      (node (ref "U7") (pin "4") (pinfunction "VIN_4") (pintype "power_in"))
    )
    (net (code "157") (name "VIN") (class "Default")
      (node (ref "J4") (pin "1") (pinfunction "1_1") (pintype "passive"))
    )
    (net (code "158") (name "VRST") (class "Default")
      (node (ref "ISP1") (pin "5") (pinfunction "RST_5") (pintype "output"))
      (node (ref "JP5") (pin "2") (pinfunction "2_2") (pintype "passive"))
      (node (ref "R13") (pin "1") (pinfunction "1_1") (pintype "passive"))
      (node (ref "S3") (pin "3") (pinfunction "3_3") (pintype "passive"))
      (node (ref "S3") (pin "4") (pinfunction "4_4") (pintype "passive"))
      (node (ref "U3") (pin "29") (pinfunction "PC6(/RESET)_29") (pintype "bidirectional"))
    )
    (net (code "159") (name "WDKICK") (class "Default")
      (node (ref "ISP1") (pin "1") (pinfunction "MISO_1") (pintype "input"))
      (node (ref "U20") (pin "4") (pinfunction "WDI_4") (pintype "bidirectional"))
      (node (ref "U3") (pin "16") (pinfunction "PB4(MISO)_16") (pintype "bidirectional"))
    )
    (net (code "160") (name "WDRX") (class "Default")
      (node (ref "U13") (pin "14") (pinfunction "A1_14") (pintype "bidirectional"))
      (node (ref "U4") (pin "6") (pinfunction "OUTB_6") (pintype "bidirectional"))
    )
    (net (code "161") (name "WDTX") (class "Default")
      (node (ref "U13") (pin "5") (pinfunction "B1_5") (pintype "bidirectional"))
      (node (ref "U4") (pin "7") (pinfunction "INA_7") (pintype "bidirectional"))
    )
    (net (code "162") (name "WIFICONECT") (class "Default")
      (node (ref "U1") (pin "22") (pinfunction "WLANLED_22") (pintype "bidirectional"))
      (node (ref "WIFI") (pin "C") (pinfunction "C_C") (pintype "passive"))
    )
    (net (code "163") (name "unconnected-(CHG-O-Pad1)") (class "Default")
      (node (ref "CHG") (pin "1") (pinfunction "O_1") (pintype "passive"))
    )
    (net (code "164") (name "unconnected-(CN1-PadID)") (class "Default")
      (node (ref "CN1") (pin "ID") (pinfunction "ID_ID") (pintype "bidirectional"))
    )
    (net (code "165") (name "unconnected-(IC1-CBUS2-Pad13)") (class "Default")
      (node (ref "IC1") (pin "13") (pinfunction "CBUS2_13") (pintype "bidirectional"))
    )
    (net (code "166") (name "unconnected-(IC1-CBUS3-Pad14)") (class "Default")
      (node (ref "IC1") (pin "14") (pinfunction "CBUS3_14") (pintype "bidirectional"))
    )
    (net (code "167") (name "unconnected-(IC1-CBUS4-Pad12)") (class "Default")
      (node (ref "IC1") (pin "12") (pinfunction "CBUS4_12") (pintype "bidirectional"))
    )
    (net (code "168") (name "unconnected-(IC1-OSCI-Pad27)") (class "Default")
      (node (ref "IC1") (pin "27") (pinfunction "OSCI_27") (pintype "input"))
    )
    (net (code "169") (name "unconnected-(IC1-OSCO-Pad28)") (class "Default")
      (node (ref "IC1") (pin "28") (pinfunction "OSCO_28") (pintype "output"))
    )
    (net (code "170") (name "unconnected-(IC1-~{CTS}-Pad11)") (class "Default")
      (node (ref "IC1") (pin "11") (pinfunction "~{CTS}_11") (pintype "input"))
    )
    (net (code "171") (name "unconnected-(IC1-~{DCD}-Pad10)") (class "Default")
      (node (ref "IC1") (pin "10") (pinfunction "~{DCD}_10") (pintype "input"))
    )
    (net (code "172") (name "unconnected-(IC1-~{DSR}-Pad9)") (class "Default")
      (node (ref "IC1") (pin "9") (pinfunction "~{DSR}_9") (pintype "input"))
    )
    (net (code "173") (name "unconnected-(IC1-~{DTR}-Pad2)") (class "Default")
      (node (ref "IC1") (pin "2") (pinfunction "~{DTR}_2") (pintype "output"))
    )
    (net (code "174") (name "unconnected-(IC1-~{RESET}-Pad19)") (class "Default")
      (node (ref "IC1") (pin "19") (pinfunction "~{RESET}_19") (pintype "input"))
    )
    (net (code "175") (name "unconnected-(IC1-~{RI}-Pad6)") (class "Default")
      (node (ref "IC1") (pin "6") (pinfunction "~{RI}_6") (pintype "input"))
    )
    (net (code "176") (name "unconnected-(IC1-~{RTS}-Pad3)") (class "Default")
      (node (ref "IC1") (pin "3") (pinfunction "~{RTS}_3") (pintype "output"))
    )
    (net (code "177") (name "unconnected-(IC2-(AD2)PA2-Pad76)") (class "Default")
      (node (ref "IC2") (pin "76") (pinfunction "(AD2)PA2_76") (pintype "bidirectional"))
    )
    (net (code "178") (name "unconnected-(IC2-(AD3)PA3-Pad75)") (class "Default")
      (node (ref "IC2") (pin "75") (pinfunction "(AD3)PA3_75") (pintype "bidirectional"))
    )
    (net (code "179") (name "unconnected-(IC2-(AD4)PA4-Pad74)") (class "Default")
      (node (ref "IC2") (pin "74") (pinfunction "(AD4)PA4_74") (pintype "bidirectional"))
    )
    (net (code "180") (name "unconnected-(IC2-(AD5)PA5-Pad73)") (class "Default")
      (node (ref "IC2") (pin "73") (pinfunction "(AD5)PA5_73") (pintype "bidirectional"))
    )
    (net (code "181") (name "unconnected-(IC2-(AD6)PA6-Pad72)") (class "Default")
      (node (ref "IC2") (pin "72") (pinfunction "(AD6)PA6_72") (pintype "bidirectional"))
    )
    (net (code "182") (name "unconnected-(IC2-(AD7)PA7-Pad71)") (class "Default")
      (node (ref "IC2") (pin "71") (pinfunction "(AD7)PA7_71") (pintype "bidirectional"))
    )
    (net (code "183") (name "unconnected-(IC2-(ALE)PG2-Pad70)") (class "Default")
      (node (ref "IC2") (pin "70") (pinfunction "(ALE)PG2_70") (pintype "bidirectional"))
    )
    (net (code "184") (name "unconnected-(IC2-(CLKO{slash}ICP3{slash}INT7)PE7-Pad9)") (class "Default")
      (node (ref "IC2") (pin "9") (pinfunction "(CLKO/ICP3/INT7)PE7_9") (pintype "bidirectional"))
    )
    (net (code "185") (name "unconnected-(IC2-(ICP1)PD4-Pad47)") (class "Default")
      (node (ref "IC2") (pin "47") (pinfunction "(ICP1)PD4_47") (pintype "bidirectional"))
    )
    (net (code "186") (name "unconnected-(IC2-(OC0B)PG5-Pad1)") (class "Default")
      (node (ref "IC2") (pin "1") (pinfunction "(OC0B)PG5_1") (pintype "bidirectional"))
    )
    (net (code "187") (name "unconnected-(IC2-(OC1B{slash}PCINT6)PB6-Pad25)") (class "Default")
      (node (ref "IC2") (pin "25") (pinfunction "(OC1B/PCINT6)PB6_25") (pintype "bidirectional"))
    )
    (net (code "188") (name "unconnected-(IC2-(OC2A{slash}PCINT4)PB4-Pad23)") (class "Default")
      (node (ref "IC2") (pin "23") (pinfunction "(OC2A/PCINT4)PB4_23") (pintype "bidirectional"))
    )
    (net (code "189") (name "unconnected-(IC2-(OC3A{slash}AIN1)PE3-Pad5)") (class "Default")
      (node (ref "IC2") (pin "5") (pinfunction "(OC3A/AIN1)PE3_5") (pintype "bidirectional"))
    )
    (net (code "190") (name "unconnected-(IC2-(OC3B{slash}INT4)PE4-Pad6)") (class "Default")
      (node (ref "IC2") (pin "6") (pinfunction "(OC3B/INT4)PE4_6") (pintype "bidirectional"))
    )
    (net (code "191") (name "unconnected-(IC2-(OC3C{slash}INT5)PE5-Pad7)") (class "Default")
      (node (ref "IC2") (pin "7") (pinfunction "(OC3C/INT5)PE5_7") (pintype "bidirectional"))
    )
    (net (code "192") (name "unconnected-(IC2-(RD)PG1-Pad52)") (class "Default")
      (node (ref "IC2") (pin "52") (pinfunction "(RD)PG1_52") (pintype "bidirectional"))
    )
    (net (code "193") (name "unconnected-(IC2-(SS{slash}PCINT0)PB0-Pad19)") (class "Default")
      (node (ref "IC2") (pin "19") (pinfunction "(SS/PCINT0)PB0_19") (pintype "bidirectional"))
    )
    (net (code "194") (name "unconnected-(IC2-(T0)PD7-Pad50)") (class "Default")
      (node (ref "IC2") (pin "50") (pinfunction "(T0)PD7_50") (pintype "bidirectional"))
    )
    (net (code "195") (name "unconnected-(IC2-(T1)PD6-Pad49)") (class "Default")
      (node (ref "IC2") (pin "49") (pinfunction "(T1)PD6_49") (pintype "bidirectional"))
    )
    (net (code "196") (name "unconnected-(IC2-(T3{slash}INT6)PE6-Pad8)") (class "Default")
      (node (ref "IC2") (pin "8") (pinfunction "(T3/INT6)PE6_8") (pintype "bidirectional"))
    )
    (net (code "197") (name "unconnected-(IC2-(TOSC1)PG4-Pad29)") (class "Default")
      (node (ref "IC2") (pin "29") (pinfunction "(TOSC1)PG4_29") (pintype "bidirectional"))
    )
    (net (code "198") (name "unconnected-(IC2-(TOSC2)PG3-Pad28)") (class "Default")
      (node (ref "IC2") (pin "28") (pinfunction "(TOSC2)PG3_28") (pintype "bidirectional"))
    )
    (net (code "199") (name "unconnected-(IC2-(WR)PG0-Pad51)") (class "Default")
      (node (ref "IC2") (pin "51") (pinfunction "(WR)PG0_51") (pintype "bidirectional"))
    )
    (net (code "200") (name "unconnected-(IC2-(XCK0{slash}AIN0)PE2-Pad4)") (class "Default")
      (node (ref "IC2") (pin "4") (pinfunction "(XCK0/AIN0)PE2_4") (pintype "bidirectional"))
    )
    (net (code "201") (name "unconnected-(IC2-(XCK1)PD5-Pad48)") (class "Default")
      (node (ref "IC2") (pin "48") (pinfunction "(XCK1)PD5_48") (pintype "bidirectional"))
    )
    (net (code "202") (name "unconnected-(IC2-AREF-Pad98)") (class "Default")
      (node (ref "IC2") (pin "98") (pinfunction "AREF_98") (pintype "bidirectional"))
    )
    (net (code "203") (name "unconnected-(IC2-PH2(XCK2)-Pad14)") (class "Default")
      (node (ref "IC2") (pin "14") (pinfunction "PH2(XCK2)_14") (pintype "bidirectional"))
    )
    (net (code "204") (name "unconnected-(IC2-PH3(OC4A)-Pad15)") (class "Default")
      (node (ref "IC2") (pin "15") (pinfunction "PH3(OC4A)_15") (pintype "bidirectional"))
    )
    (net (code "205") (name "unconnected-(IC2-PH4(OC4B)-Pad16)") (class "Default")
      (node (ref "IC2") (pin "16") (pinfunction "PH4(OC4B)_16") (pintype "bidirectional"))
    )
    (net (code "206") (name "unconnected-(IC2-PH5(OC4C)-Pad17)") (class "Default")
      (node (ref "IC2") (pin "17") (pinfunction "PH5(OC4C)_17") (pintype "bidirectional"))
    )
    (net (code "207") (name "unconnected-(IC2-PH6(OC2B)-Pad18)") (class "Default")
      (node (ref "IC2") (pin "18") (pinfunction "PH6(OC2B)_18") (pintype "bidirectional"))
    )
    (net (code "208") (name "unconnected-(IC2-PH7(T4)-Pad27)") (class "Default")
      (node (ref "IC2") (pin "27") (pinfunction "PH7(T4)_27") (pintype "bidirectional"))
    )
    (net (code "209") (name "unconnected-(IC2-PJ2(XCK3{slash}PCINT11)-Pad65)") (class "Default")
      (node (ref "IC2") (pin "65") (pinfunction "PJ2(XCK3/PCINT11)_65") (pintype "bidirectional"))
    )
    (net (code "210") (name "unconnected-(IC2-PJ3(PCINT12)-Pad66)") (class "Default")
      (node (ref "IC2") (pin "66") (pinfunction "PJ3(PCINT12)_66") (pintype "bidirectional"))
    )
    (net (code "211") (name "unconnected-(IC2-PJ4(PCINT13)-Pad67)") (class "Default")
      (node (ref "IC2") (pin "67") (pinfunction "PJ4(PCINT13)_67") (pintype "bidirectional"))
    )
    (net (code "212") (name "unconnected-(IC2-PJ5(PCINT14)-Pad68)") (class "Default")
      (node (ref "IC2") (pin "68") (pinfunction "PJ5(PCINT14)_68") (pintype "bidirectional"))
    )
    (net (code "213") (name "unconnected-(IC2-PJ6(PCINT15)-Pad69)") (class "Default")
      (node (ref "IC2") (pin "69") (pinfunction "PJ6(PCINT15)_69") (pintype "bidirectional"))
    )
    (net (code "214") (name "unconnected-(IC2-PJ7-Pad79)") (class "Default")
      (node (ref "IC2") (pin "79") (pinfunction "PJ7_79") (pintype "bidirectional"))
    )
    (net (code "215") (name "unconnected-(IC2-PL0(ICP4)-Pad35)") (class "Default")
      (node (ref "IC2") (pin "35") (pinfunction "PL0(ICP4)_35") (pintype "bidirectional"))
    )
    (net (code "216") (name "unconnected-(IC2-PL1(ICP5)-Pad36)") (class "Default")
      (node (ref "IC2") (pin "36") (pinfunction "PL1(ICP5)_36") (pintype "bidirectional"))
    )
    (net (code "217") (name "unconnected-(IC2-PL2(T5)-Pad37)") (class "Default")
      (node (ref "IC2") (pin "37") (pinfunction "PL2(T5)_37") (pintype "bidirectional"))
    )
    (net (code "218") (name "unconnected-(IC2-PL3(OC5A)-Pad38)") (class "Default")
      (node (ref "IC2") (pin "38") (pinfunction "PL3(OC5A)_38") (pintype "bidirectional"))
    )
    (net (code "219") (name "unconnected-(IC2-PL4(OC5B)-Pad39)") (class "Default")
      (node (ref "IC2") (pin "39") (pinfunction "PL4(OC5B)_39") (pintype "bidirectional"))
    )
    (net (code "220") (name "unconnected-(IC2-PL5(OC5C)-Pad40)") (class "Default")
      (node (ref "IC2") (pin "40") (pinfunction "PL5(OC5C)_40") (pintype "bidirectional"))
    )
    (net (code "221") (name "unconnected-(IC2-PL6-Pad41)") (class "Default")
      (node (ref "IC2") (pin "41") (pinfunction "PL6_41") (pintype "bidirectional"))
    )
    (net (code "222") (name "unconnected-(IC2-PL7-Pad42)") (class "Default")
      (node (ref "IC2") (pin "42") (pinfunction "PL7_42") (pintype "bidirectional"))
    )
    (net (code "223") (name "unconnected-(JP7-Pad1)") (class "Default")
      (node (ref "JP7") (pin "1") (pinfunction "1_1") (pintype "passive"))
    )
    (net (code "224") (name "unconnected-(U1-CP1-Pad13)") (class "Default")
      (node (ref "U1") (pin "13") (pinfunction "CP1_13") (pintype "bidirectional"))
    )
    (net (code "225") (name "unconnected-(U1-CP2-Pad15)") (class "Default")
      (node (ref "U1") (pin "15") (pinfunction "CP2_15") (pintype "bidirectional"))
    )
    (net (code "226") (name "unconnected-(U1-CP3-Pad17)") (class "Default")
      (node (ref "U1") (pin "17") (pinfunction "CP3_17") (pintype "bidirectional"))
    )
    (net (code "227") (name "unconnected-(U1-CP4-Pad19)") (class "Default")
      (node (ref "U1") (pin "19") (pinfunction "CP4_19") (pintype "bidirectional"))
    )
    (net (code "228") (name "unconnected-(U1-CP5-Pad29)") (class "Default")
      (node (ref "U1") (pin "29") (pinfunction "CP5_29") (pintype "bidirectional"))
    )
    (net (code "229") (name "unconnected-(U1-CP6-Pad31)") (class "Default")
      (node (ref "U1") (pin "31") (pinfunction "CP6_31") (pintype "bidirectional"))
    )
    (net (code "230") (name "unconnected-(U1-CP7-Pad33)") (class "Default")
      (node (ref "U1") (pin "33") (pinfunction "CP7_33") (pintype "bidirectional"))
    )
    (net (code "231") (name "unconnected-(U1-CP8-Pad35)") (class "Default")
      (node (ref "U1") (pin "35") (pinfunction "CP8_35") (pintype "bidirectional"))
    )
    (net (code "232") (name "unconnected-(U1-CTS1-Pad11)") (class "Default")
      (node (ref "U1") (pin "11") (pinfunction "CTS1_11") (pintype "bidirectional"))
    )
    (net (code "233") (name "unconnected-(U1-CTS2-Pad27)") (class "Default")
      (node (ref "U1") (pin "27") (pinfunction "CTS2_27") (pintype "bidirectional"))
    )
    (net (code "234") (name "unconnected-(U1-RTS1-Pad7)") (class "Default")
      (node (ref "U1") (pin "7") (pinfunction "RTS1_7") (pintype "bidirectional"))
    )
    (net (code "235") (name "unconnected-(U1-RTS2-Pad23)") (class "Default")
      (node (ref "U1") (pin "23") (pinfunction "RTS2_23") (pintype "bidirectional"))
    )
    (net (code "236") (name "unconnected-(U1-RX2-Pad25)") (class "Default")
      (node (ref "U1") (pin "25") (pinfunction "RX2_25") (pintype "bidirectional"))
    )
    (net (code "237") (name "unconnected-(U1-TX2-Pad21)") (class "Default")
      (node (ref "U1") (pin "21") (pinfunction "TX2_21") (pintype "bidirectional"))
    )
    (net (code "238") (name "unconnected-(U3-ADC6-Pad19)") (class "Default")
      (node (ref "U3") (pin "19") (pinfunction "ADC6_19") (pintype "bidirectional"))
    )
    (net (code "239") (name "unconnected-(U3-ADC7-Pad22)") (class "Default")
      (node (ref "U3") (pin "22") (pinfunction "ADC7_22") (pintype "bidirectional"))
    )
    (net (code "240") (name "unconnected-(U3-AREF-Pad20)") (class "Default")
      (node (ref "U3") (pin "20") (pinfunction "AREF_20") (pintype "bidirectional"))
    )
    (net (code "241") (name "unconnected-(U3-PB0(ICP)-Pad12)") (class "Default")
      (node (ref "U3") (pin "12") (pinfunction "PB0(ICP)_12") (pintype "bidirectional"))
    )
    (net (code "242") (name "unconnected-(U3-PB1(OC1A)-Pad13)") (class "Default")
      (node (ref "U3") (pin "13") (pinfunction "PB1(OC1A)_13") (pintype "bidirectional"))
    )
    (net (code "243") (name "unconnected-(U3-PB2(SS{slash}OC1B)-Pad14)") (class "Default")
      (node (ref "U3") (pin "14") (pinfunction "PB2(SS/OC1B)_14") (pintype "bidirectional"))
    )
    (net (code "244") (name "unconnected-(U3-PC4(ADC4{slash}SDA)-Pad27)") (class "Default")
      (node (ref "U3") (pin "27") (pinfunction "PC4(ADC4/SDA)_27") (pintype "bidirectional"))
    )
    (net (code "245") (name "unconnected-(U3-PC5(ADC5{slash}SCL)-Pad28)") (class "Default")
      (node (ref "U3") (pin "28") (pinfunction "PC5(ADC5/SCL)_28") (pintype "bidirectional"))
    )
    (net (code "246") (name "unconnected-(U3-PD7(AIN1)-Pad11)") (class "Default")
      (node (ref "U3") (pin "11") (pinfunction "PD7(AIN1)_11") (pintype "bidirectional"))
    )
    (net (code "247") (name "unconnected-(U5-IN2-Pad4)") (class "Default")
      (node (ref "U5") (pin "4") (pinfunction "IN2_4") (pintype "bidirectional"))
    )
    (net (code "248") (name "unconnected-(U6-ADC6-Pad19)") (class "Default")
      (node (ref "U6") (pin "19") (pinfunction "ADC6_19") (pintype "bidirectional"))
    )
    (net (code "249") (name "unconnected-(U6-ADC7-Pad22)") (class "Default")
      (node (ref "U6") (pin "22") (pinfunction "ADC7_22") (pintype "bidirectional"))
    )
    (net (code "250") (name "unconnected-(U6-AREF-Pad20)") (class "Default")
      (node (ref "U6") (pin "20") (pinfunction "AREF_20") (pintype "bidirectional"))
    )
    (net (code "251") (name "unconnected-(U6-PB0(ICP)-Pad12)") (class "Default")
      (node (ref "U6") (pin "12") (pinfunction "PB0(ICP)_12") (pintype "bidirectional"))
    )
    (net (code "252") (name "unconnected-(U6-PB1(OC1A)-Pad13)") (class "Default")
      (node (ref "U6") (pin "13") (pinfunction "PB1(OC1A)_13") (pintype "bidirectional"))
    )
    (net (code "253") (name "unconnected-(U6-PB2(SS{slash}OC1B)-Pad14)") (class "Default")
      (node (ref "U6") (pin "14") (pinfunction "PB2(SS/OC1B)_14") (pintype "bidirectional"))
    )
    (net (code "254") (name "unconnected-(U6-PC0(ADC0)-Pad23)") (class "Default")
      (node (ref "U6") (pin "23") (pinfunction "PC0(ADC0)_23") (pintype "bidirectional"))
    )
    (net (code "255") (name "unconnected-(U6-PC1(ADC1)-Pad24)") (class "Default")
      (node (ref "U6") (pin "24") (pinfunction "PC1(ADC1)_24") (pintype "bidirectional"))
    )
    (net (code "256") (name "unconnected-(U6-PC2(ADC2)-Pad25)") (class "Default")
      (node (ref "U6") (pin "25") (pinfunction "PC2(ADC2)_25") (pintype "bidirectional"))
    )
    (net (code "257") (name "unconnected-(U6-PC3(ADC3)-Pad26)") (class "Default")
      (node (ref "U6") (pin "26") (pinfunction "PC3(ADC3)_26") (pintype "bidirectional"))
    )
    (net (code "258") (name "unconnected-(U6-PC4(ADC4{slash}SDA)-Pad27)") (class "Default")
      (node (ref "U6") (pin "27") (pinfunction "PC4(ADC4/SDA)_27") (pintype "bidirectional"))
    )
    (net (code "259") (name "unconnected-(U6-PC5(ADC5{slash}SCL)-Pad28)") (class "Default")
      (node (ref "U6") (pin "28") (pinfunction "PC5(ADC5/SCL)_28") (pintype "bidirectional"))
    )
    (net (code "260") (name "unconnected-(U6-PD6(AIN0)-Pad10)") (class "Default")
      (node (ref "U6") (pin "10") (pinfunction "PD6(AIN0)_10") (pintype "bidirectional"))
    )
    (net (code "261") (name "unconnected-(U6-PD7(AIN1)-Pad11)") (class "Default")
      (node (ref "U6") (pin "11") (pinfunction "PD7(AIN1)_11") (pintype "bidirectional"))
    )
    (net (code "262") (name "unconnected-(U13-B3-Pad4)") (class "Default")
      (node (ref "U13") (pin "4") (pinfunction "B3_4") (pintype "bidirectional"))
    )
    (net (code "263") (name "unconnected-(U20-~{MR}-Pad3)") (class "Default")
      (node (ref "U20") (pin "3") (pinfunction "~{MR}_3") (pintype "bidirectional"))
    )
    (net (code "264") (name "unconnected-(VREG-BP-Pad4)") (class "Default")
      (node (ref "VREG") (pin "4") (pinfunction "BP_4") (pintype "input"))
    )
    (net (code "265") (name "~{FAULT}") (class "Default")
      (node (ref "IC2") (pin "24") (pinfunction "(OC1A/PCINT5)PB5_24") (pintype "bidirectional"))
    )
    (net (code "266") (name "~{RESET}") (class "Default")
      (node (ref "C20") (pin "1") (pinfunction "1_1") (pintype "passive"))
      (node (ref "IC2") (pin "30") (pinfunction "RESET_30") (pintype "input"))
      (node (ref "ICSP") (pin "5") (pinfunction "5_5") (pintype "passive"))
      (node (ref "R26") (pin "1") (pinfunction "1_1") (pintype "passive"))
      (node (ref "S1") (pin "1") (pinfunction "1_1") (pintype "passive"))
      (node (ref "S1") (pin "2") (pinfunction "2_2") (pintype "passive"))
    )
    (net (code "267") (name "~{REST}") (class "Default")
      (node (ref "ISP2") (pin "5") (pinfunction "RST_5") (pintype "output"))
      (node (ref "R15") (pin "1") (pinfunction "1_1") (pintype "passive"))
      (node (ref "S2") (pin "3") (pinfunction "3_3") (pintype "passive"))
      (node (ref "S2") (pin "4") (pinfunction "4_4") (pintype "passive"))
      (node (ref "U6") (pin "29") (pinfunction "PC6(/RESET)_29") (pintype "bidirectional"))
    )
    (net (code "268") (name "~{RST}") (class "Default")
      (node (ref "U1") (pin "1") (pinfunction "~{RESET}_1") (pintype "bidirectional"))
    )
  )
)
